# diagram.net
KiCad netlist of a schematic drawn in EasyEDA
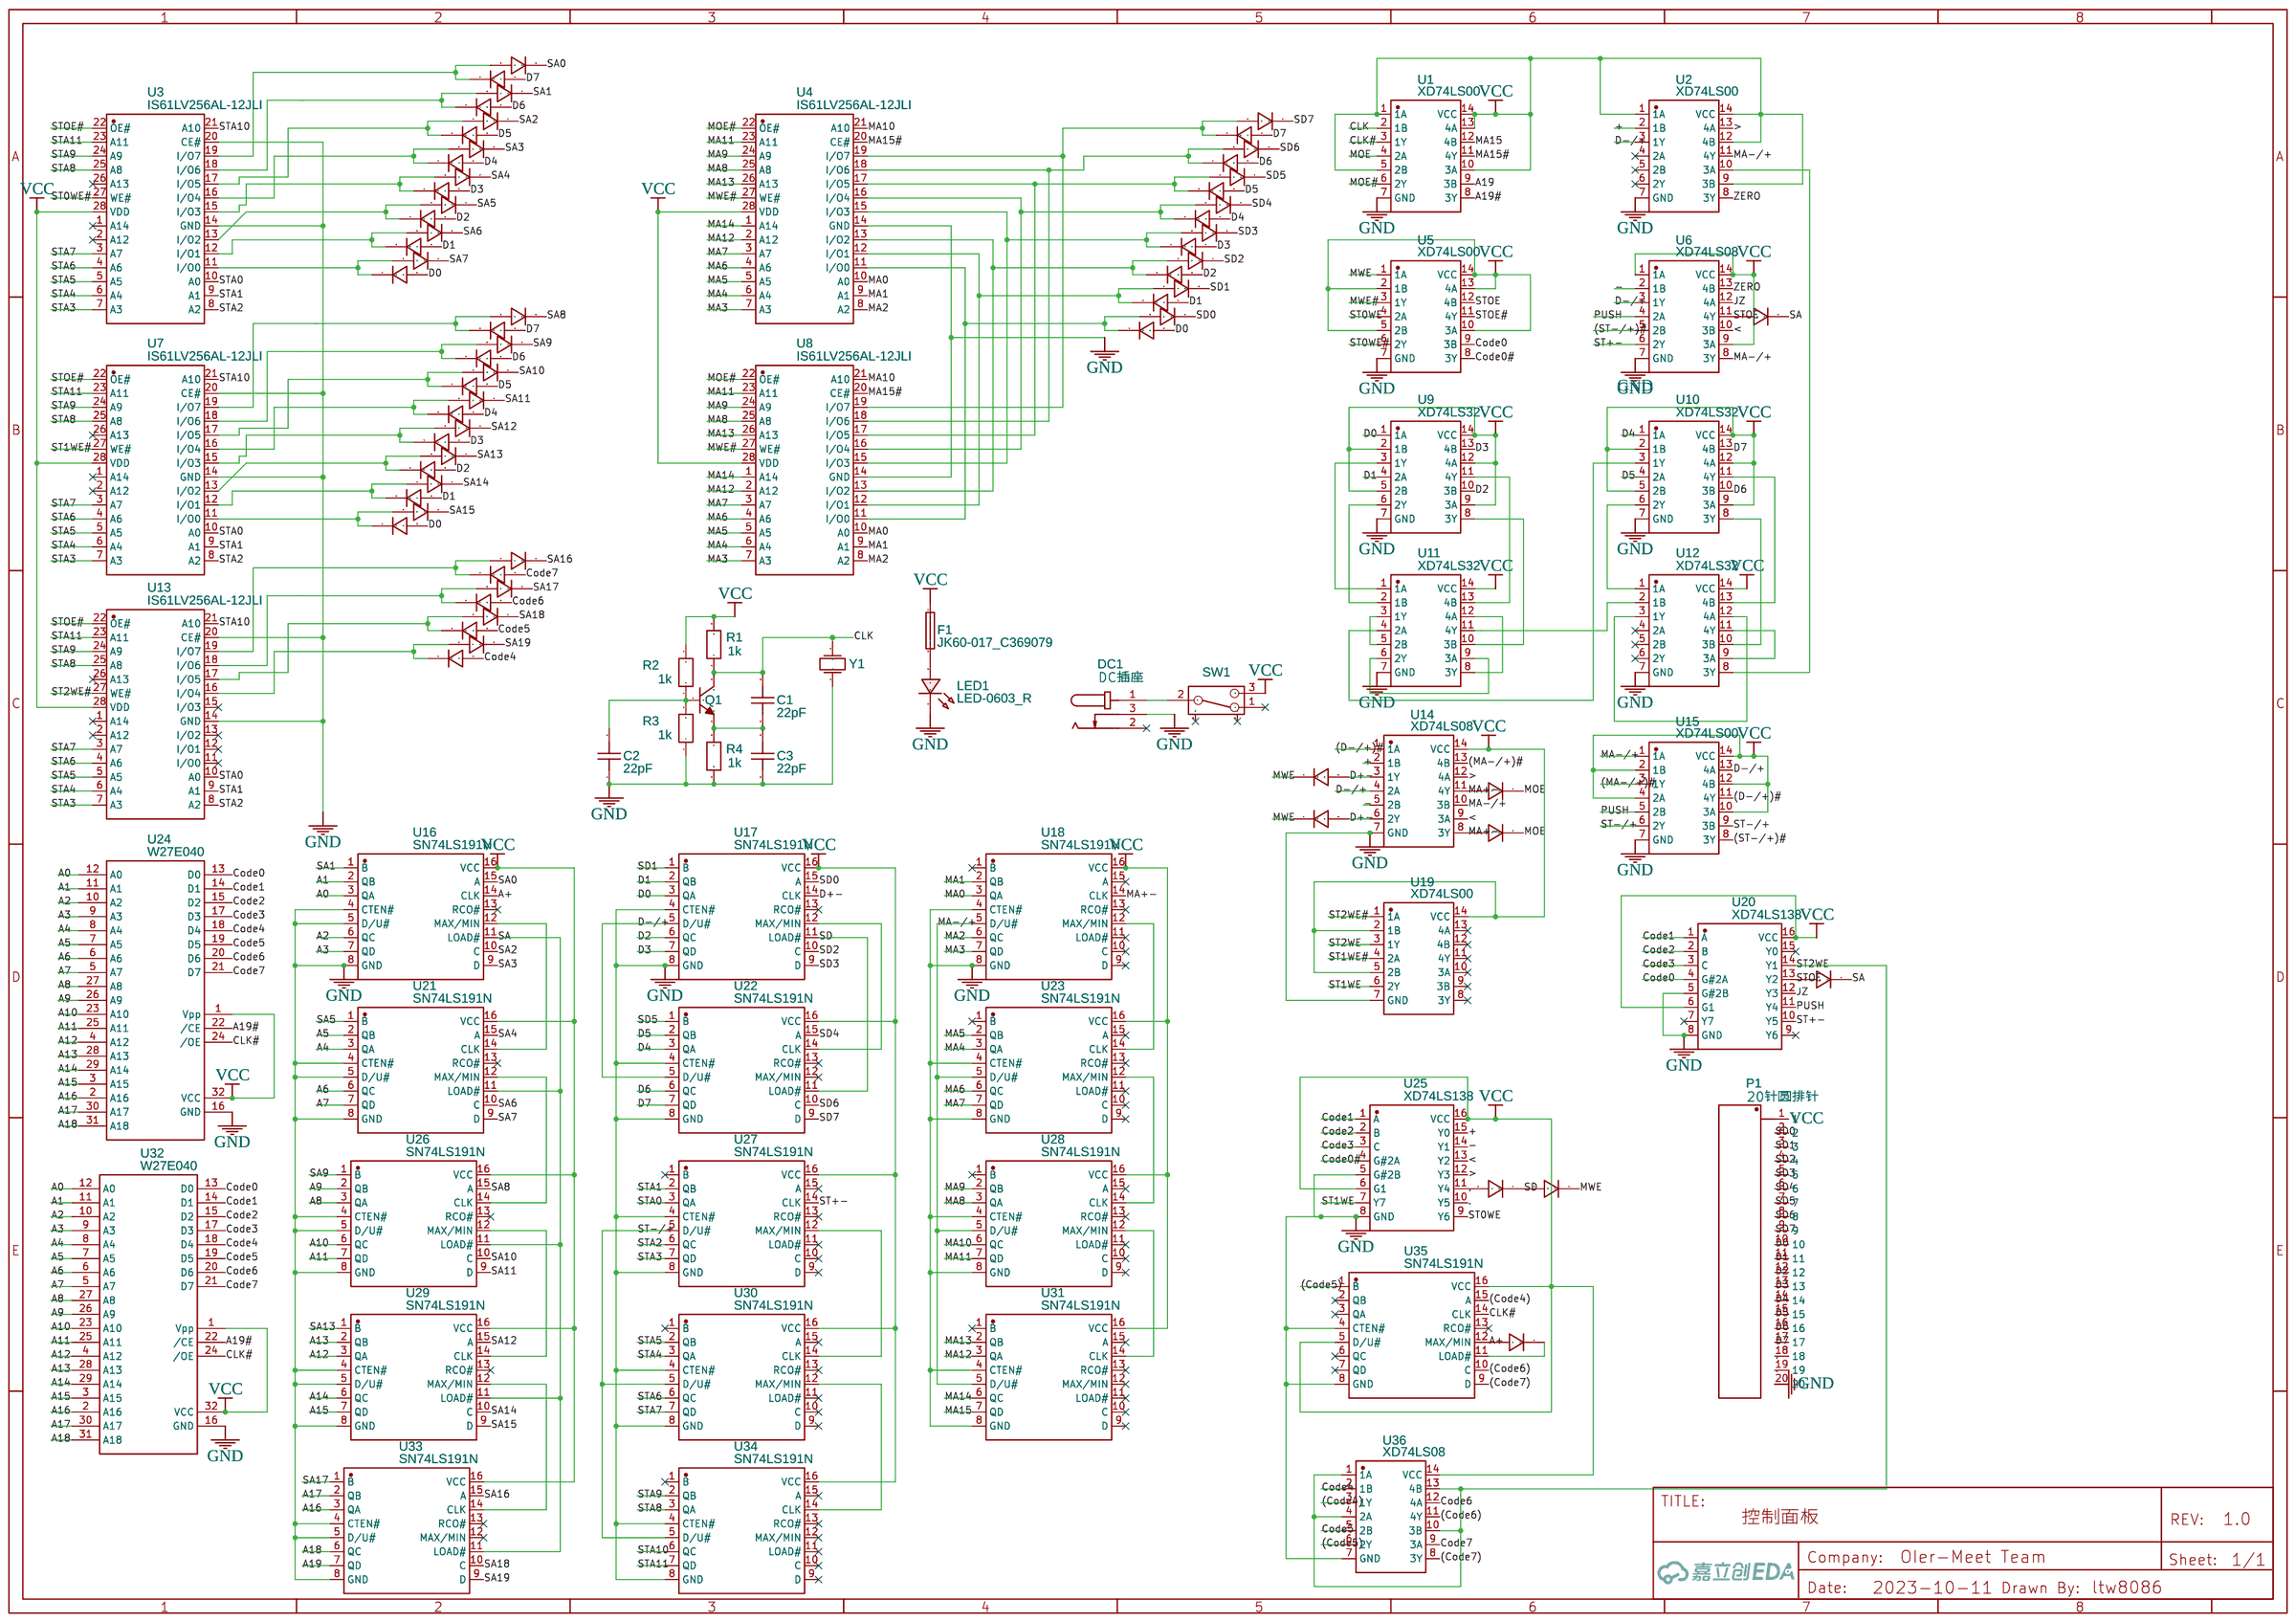
[diagram p0: schematic sheet]

(export (version "E")
  (design (tool "Eeschema 10.0.6"))
  (components
    (comp (ref "C1") (value "22pF") (libsource (lib "") (part "C_RAD-0.2_US")))
    (comp (ref "C2") (value "22pF") (libsource (lib "") (part "C_RAD-0.2_US")))
    (comp (ref "C3") (value "22pF") (libsource (lib "") (part "C_RAD-0.2_US")))
    (comp (ref "D1")
      (value "1N4148")
      (fields (field (name "Manufacturer") "STMicroelectronics"))
      (libsource (lib "") (part "1N4007"))
    )
    (comp (ref "D2")
      (value "1N4148")
      (fields (field (name "Manufacturer") "STMicroelectronics"))
      (libsource (lib "") (part "1N4148"))
    )
    (comp (ref "D3")
      (value "1N4148")
      (fields (field (name "Manufacturer") "STMicroelectronics"))
      (libsource (lib "") (part "1N4007"))
    )
    (comp (ref "D4")
      (value "1N4148")
      (fields (field (name "Manufacturer") "STMicroelectronics"))
      (libsource (lib "") (part "1N4148"))
    )
    (comp (ref "D5")
      (value "1N4148")
      (fields (field (name "Manufacturer") "STMicroelectronics"))
      (libsource (lib "") (part "1N4007"))
    )
    (comp (ref "D6")
      (value "1N4148")
      (fields (field (name "Manufacturer") "STMicroelectronics"))
      (libsource (lib "") (part "1N4007"))
    )
    (comp (ref "D7")
      (value "1N4148")
      (fields (field (name "Manufacturer") "STMicroelectronics"))
      (libsource (lib "") (part "1N4148"))
    )
    (comp (ref "D8")
      (value "1N4148")
      (fields (field (name "Manufacturer") "STMicroelectronics"))
      (libsource (lib "") (part "1N4148"))
    )
    (comp (ref "D9")
      (value "1N4148")
      (fields (field (name "Manufacturer") "STMicroelectronics"))
      (libsource (lib "") (part "1N4007"))
    )
    (comp (ref "D10")
      (value "1N4148")
      (fields (field (name "Manufacturer") "STMicroelectronics"))
      (libsource (lib "") (part "1N4007"))
    )
    (comp (ref "D11")
      (value "1N4148")
      (fields (field (name "Manufacturer") "STMicroelectronics"))
      (libsource (lib "") (part "1N4148"))
    )
    (comp (ref "D12")
      (value "1N4148")
      (fields (field (name "Manufacturer") "STMicroelectronics"))
      (libsource (lib "") (part "1N4148"))
    )
    (comp (ref "D13")
      (value "1N4148")
      (fields (field (name "Manufacturer") "STMicroelectronics"))
      (libsource (lib "") (part "1N4007"))
    )
    (comp (ref "D14")
      (value "1N4148")
      (fields (field (name "Manufacturer") "STMicroelectronics"))
      (libsource (lib "") (part "1N4007"))
    )
    (comp (ref "D15")
      (value "1N4148")
      (fields (field (name "Manufacturer") "STMicroelectronics"))
      (libsource (lib "") (part "1N4148"))
    )
    (comp (ref "D16")
      (value "1N4148")
      (fields (field (name "Manufacturer") "STMicroelectronics"))
      (libsource (lib "") (part "1N4148"))
    )
    (comp (ref "D17")
      (value "1N4148")
      (fields (field (name "Manufacturer") "STMicroelectronics"))
      (libsource (lib "") (part "1N4007"))
    )
    (comp (ref "D18")
      (value "1N4148")
      (fields (field (name "Manufacturer") "STMicroelectronics"))
      (libsource (lib "") (part "1N4007"))
    )
    (comp (ref "D19")
      (value "1N4148")
      (fields (field (name "Manufacturer") "STMicroelectronics"))
      (libsource (lib "") (part "1N4148"))
    )
    (comp (ref "D20")
      (value "1N4148")
      (fields (field (name "Manufacturer") "STMicroelectronics"))
      (libsource (lib "") (part "1N4148"))
    )
    (comp (ref "D21")
      (value "1N4148")
      (fields (field (name "Manufacturer") "STMicroelectronics"))
      (libsource (lib "") (part "1N4007"))
    )
    (comp (ref "D22")
      (value "1N4148")
      (fields (field (name "Manufacturer") "STMicroelectronics"))
      (libsource (lib "") (part "1N4007"))
    )
    (comp (ref "D23")
      (value "1N4148")
      (fields (field (name "Manufacturer") "STMicroelectronics"))
      (libsource (lib "") (part "1N4148"))
    )
    (comp (ref "D24")
      (value "1N4148")
      (fields (field (name "Manufacturer") "STMicroelectronics"))
      (libsource (lib "") (part "1N4148"))
    )
    (comp (ref "D25")
      (value "1N4148")
      (fields (field (name "Manufacturer") "STMicroelectronics"))
      (libsource (lib "") (part "1N4007"))
    )
    (comp (ref "D26")
      (value "1N4148")
      (fields (field (name "Manufacturer") "STMicroelectronics"))
      (libsource (lib "") (part "1N4007"))
    )
    (comp (ref "D27")
      (value "1N4148")
      (fields (field (name "Manufacturer") "STMicroelectronics"))
      (libsource (lib "") (part "1N4148"))
    )
    (comp (ref "D28")
      (value "1N4148")
      (fields (field (name "Manufacturer") "STMicroelectronics"))
      (libsource (lib "") (part "1N4148"))
    )
    (comp (ref "D29")
      (value "1N4148")
      (fields (field (name "Manufacturer") "STMicroelectronics"))
      (libsource (lib "") (part "1N4007"))
    )
    (comp (ref "D30")
      (value "1N4148")
      (fields (field (name "Manufacturer") "STMicroelectronics"))
      (libsource (lib "") (part "1N4148"))
    )
    (comp (ref "D31")
      (value "1N4148")
      (fields (field (name "Manufacturer") "STMicroelectronics"))
      (libsource (lib "") (part "1N4007"))
    )
    (comp (ref "D32")
      (value "1N4148")
      (fields (field (name "Manufacturer") "STMicroelectronics"))
      (libsource (lib "") (part "1N4007"))
    )
    (comp (ref "D33")
      (value "1N4148")
      (fields (field (name "Manufacturer") "STMicroelectronics"))
      (libsource (lib "") (part "1N4148"))
    )
    (comp (ref "D34")
      (value "1N4148")
      (fields (field (name "Manufacturer") "STMicroelectronics"))
      (libsource (lib "") (part "1N4148"))
    )
    (comp (ref "D35")
      (value "1N4148")
      (fields (field (name "Manufacturer") "STMicroelectronics"))
      (libsource (lib "") (part "1N4007"))
    )
    (comp (ref "D36")
      (value "1N4148")
      (fields (field (name "Manufacturer") "STMicroelectronics"))
      (libsource (lib "") (part "1N4148"))
    )
    (comp (ref "D37")
      (value "1N4148")
      (fields (field (name "Manufacturer") "STMicroelectronics"))
      (libsource (lib "") (part "1N4007"))
    )
    (comp (ref "D38")
      (value "1N4148")
      (fields (field (name "Manufacturer") "STMicroelectronics"))
      (libsource (lib "") (part "1N4148"))
    )
    (comp (ref "D39")
      (value "1N4148")
      (fields (field (name "Manufacturer") "STMicroelectronics"))
      (libsource (lib "") (part "1N4007"))
    )
    (comp (ref "D40")
      (value "1N4148")
      (fields (field (name "Manufacturer") "STMicroelectronics"))
      (libsource (lib "") (part "1N4148"))
    )
    (comp (ref "D41")
      (value "1N4148")
      (fields (field (name "Manufacturer") "STMicroelectronics"))
      (libsource (lib "") (part "1N4007"))
    )
    (comp (ref "D42")
      (value "1N4148")
      (fields (field (name "Manufacturer") "STMicroelectronics"))
      (libsource (lib "") (part "1N4148"))
    )
    (comp (ref "D43")
      (value "1N4148")
      (fields (field (name "Manufacturer") "STMicroelectronics"))
      (libsource (lib "") (part "1N4007"))
    )
    (comp (ref "D44")
      (value "1N4148")
      (fields (field (name "Manufacturer") "STMicroelectronics"))
      (libsource (lib "") (part "1N4148"))
    )
    (comp (ref "D45")
      (value "1N4148")
      (fields (field (name "Manufacturer") "STMicroelectronics"))
      (libsource (lib "") (part "1N4007"))
    )
    (comp (ref "D46")
      (value "1N4148")
      (fields (field (name "Manufacturer") "STMicroelectronics"))
      (libsource (lib "") (part "1N4148"))
    )
    (comp (ref "D47")
      (value "1N4148")
      (fields (field (name "Manufacturer") "STMicroelectronics"))
      (libsource (lib "") (part "1N4007"))
    )
    (comp (ref "D48")
      (value "1N4148")
      (fields (field (name "Manufacturer") "STMicroelectronics"))
      (libsource (lib "") (part "1N4148"))
    )
    (comp (ref "D49")
      (value "1N4148")
      (fields (field (name "Manufacturer") "STMicroelectronics"))
      (libsource (lib "") (part "1N4007"))
    )
    (comp (ref "D50")
      (value "1N4148")
      (fields (field (name "Manufacturer") "STMicroelectronics"))
      (libsource (lib "") (part "1N4148"))
    )
    (comp (ref "D51")
      (value "1N4148")
      (fields (field (name "Manufacturer") "STMicroelectronics"))
      (libsource (lib "") (part "1N4007"))
    )
    (comp (ref "D52")
      (value "1N4148")
      (fields (field (name "Manufacturer") "STMicroelectronics"))
      (libsource (lib "") (part "1N4148"))
    )
    (comp (ref "D53")
      (value "1N4148")
      (fields (field (name "Manufacturer") "STMicroelectronics"))
      (libsource (lib "") (part "1N4007"))
    )
    (comp (ref "D54")
      (value "1N4148")
      (fields (field (name "Manufacturer") "STMicroelectronics"))
      (libsource (lib "") (part "1N4148"))
    )
    (comp (ref "D55")
      (value "1N4148")
      (fields (field (name "Manufacturer") "STMicroelectronics"))
      (libsource (lib "") (part "1N4007"))
    )
    (comp (ref "D56")
      (value "1N4148")
      (fields (field (name "Manufacturer") "STMicroelectronics"))
      (libsource (lib "") (part "1N4148"))
    )
    (comp (ref "D57")
      (value "1N4148")
      (fields (field (name "Manufacturer") "STMicroelectronics"))
      (libsource (lib "") (part "1N4148"))
    )
    (comp (ref "D58")
      (value "1N4148")
      (fields (field (name "Manufacturer") "STMicroelectronics"))
      (libsource (lib "") (part "1N4148"))
    )
    (comp (ref "D62")
      (value "1N4148")
      (fields (field (name "Manufacturer") "STMicroelectronics"))
      (libsource (lib "") (part "1N4007"))
    )
    (comp (ref "D63")
      (value "1N4148")
      (fields (field (name "Manufacturer") "STMicroelectronics"))
      (libsource (lib "") (part "1N4007"))
    )
    (comp (ref "D64")
      (value "1N4148")
      (fields (field (name "Manufacturer") "STMicroelectronics"))
      (libsource (lib "") (part "1N4007"))
    )
    (comp (ref "D65")
      (value "1N4148")
      (fields (field (name "Manufacturer") "STMicroelectronics"))
      (libsource (lib "") (part "1N4007"))
    )
    (comp (ref "D66")
      (value "1N4148")
      (fields (field (name "Manufacturer") "STMicroelectronics"))
      (libsource (lib "") (part "1N4148_1"))
    )
    (comp (ref "D67")
      (value "1N4148")
      (fields (field (name "Manufacturer") "STMicroelectronics"))
      (libsource (lib "") (part "1N4007"))
    )
    (comp (ref "D68")
      (value "1N4148")
      (fields (field (name "Manufacturer") "STMicroelectronics"))
      (libsource (lib "") (part "1N4148_1"))
    )
    (comp (ref "DC1")
      (value "DC插座")
      (fields
        (field (name "Manufacturer Part") "DC-005-5A-2.0")
        (field (name "Manufacturer") "XKB Enterprise")
      )
      (libsource (lib "") (part "DC插座"))
    )
    (comp (ref "F1")
      (value "JK60-017_C369079")
      (fields (field (name "Manufacturer Part") "JK60-017") (field (name "Manufacturer") "JK(金科)"))
      (libsource (lib "") (part "JK60-017_C369079"))
    )
    (comp (ref "LED1")
      (value "LED-0603_R")
      (fields
        (field (name "Manufacturer Part") "19-217/R6C-AL1M2VY/3T")
        (field (name "Manufacturer") "EVERLIGHT(台湾亿光)")
      )
      (libsource (lib "") (part "LED-0603_R"))
    )
    (comp (ref "P1")
      (value "20针圆排针")
      (fields (field (name "Manufacturer") "BOOMELE"))
      (libsource (lib "") (part "20针圆排针"))
    )
    (comp (ref "Q1")
      (value "2N3904(TO-92)")
      (fields (field (name "Manufacturer Part") "2N3904") (field (name "Manufacturer") "SEMTECH"))
      (libsource (lib "") (part "2N3904(TO-92)"))
    )
    (comp (ref "R1") (value "1k") (libsource (lib "") (part "R_AXIAL-0.8_EU")))
    (comp (ref "R2") (value "1k") (libsource (lib "") (part "R_AXIAL-0.8_EU")))
    (comp (ref "R3") (value "1k") (libsource (lib "") (part "R_AXIAL-0.8_EU")))
    (comp (ref "R4") (value "1k") (libsource (lib "") (part "R_AXIAL-0.8_EU")))
    (comp (ref "SW1")
      (value "SK-12D02-VG5")
      (fields (field (name "Manufacturer") "Rectangular Connectors - Contacts"))
      (libsource (lib "") (part "SK-12D02-VG5"))
    )
    (comp (ref "U1")
      (value "XD74LS00")
      (fields (field (name "Manufacturer") "XINLUDA(信路达)"))
      (libsource (lib "") (part "XD74LS00"))
    )
    (comp (ref "U2")
      (value "XD74LS00")
      (fields (field (name "Manufacturer") "XINLUDA(信路达)"))
      (libsource (lib "") (part "XD74LS00"))
    )
    (comp (ref "U3")
      (value "IS61LV256AL-12JLI")
      (fields (field (name "Manufacturer") "ISSI(美国芯成)"))
      (libsource (lib "") (part "IS61LV256AL-10TLI"))
    )
    (comp (ref "U4")
      (value "IS61LV256AL-12JLI")
      (fields (field (name "Manufacturer") "ISSI(美国芯成)"))
      (libsource (lib "") (part "IS61LV256AL-10TLI"))
    )
    (comp (ref "U5")
      (value "XD74LS00")
      (fields (field (name "Manufacturer") "XINLUDA(信路达)"))
      (libsource (lib "") (part "XD74LS00"))
    )
    (comp (ref "U6")
      (value "XD74LS08")
      (fields (field (name "Manufacturer") "XINLUDA(信路达)"))
      (libsource (lib "") (part "XD74LS08"))
    )
    (comp (ref "U7")
      (value "IS61LV256AL-12JLI")
      (fields (field (name "Manufacturer") "ISSI(美国芯成)"))
      (libsource (lib "") (part "IS61LV256AL-10TLI"))
    )
    (comp (ref "U8")
      (value "IS61LV256AL-12JLI")
      (fields (field (name "Manufacturer") "ISSI(美国芯成)"))
      (libsource (lib "") (part "IS61LV256AL-10TLI"))
    )
    (comp (ref "U9")
      (value "XD74LS32")
      (fields (field (name "Manufacturer") "XINLUDA(信路达)"))
      (libsource (lib "") (part "XD74LS32"))
    )
    (comp (ref "U10")
      (value "XD74LS32")
      (fields (field (name "Manufacturer") "XINLUDA(信路达)"))
      (libsource (lib "") (part "XD74LS32"))
    )
    (comp (ref "U11")
      (value "XD74LS32")
      (fields (field (name "Manufacturer") "XINLUDA(信路达)"))
      (libsource (lib "") (part "XD74LS32"))
    )
    (comp (ref "U12")
      (value "XD74LS32")
      (fields (field (name "Manufacturer") "XINLUDA(信路达)"))
      (libsource (lib "") (part "XD74LS32"))
    )
    (comp (ref "U13")
      (value "IS61LV256AL-12JLI")
      (fields (field (name "Manufacturer") "ISSI(美国芯成)"))
      (libsource (lib "") (part "IS61LV256AL-10TLI"))
    )
    (comp (ref "U14")
      (value "XD74LS08")
      (fields (field (name "Manufacturer") "XINLUDA(信路达)"))
      (libsource (lib "") (part "XD74LS08"))
    )
    (comp (ref "U15")
      (value "XD74LS00")
      (fields (field (name "Manufacturer") "XINLUDA(信路达)"))
      (libsource (lib "") (part "XD74LS00"))
    )
    (comp (ref "U16")
      (value "SN74LS191N")
      (fields (field (name "Manufacturer") "TI(德州仪器)"))
      (libsource (lib "") (part "SN74LS191N"))
    )
    (comp (ref "U17")
      (value "SN74LS191N")
      (fields (field (name "Manufacturer") "TI(德州仪器)"))
      (libsource (lib "") (part "SN74LS191N"))
    )
    (comp (ref "U18")
      (value "SN74LS191N")
      (fields (field (name "Manufacturer") "TI(德州仪器)"))
      (libsource (lib "") (part "SN74LS191N"))
    )
    (comp (ref "U19")
      (value "XD74LS00")
      (fields (field (name "Manufacturer") "XINLUDA(信路达)"))
      (libsource (lib "") (part "XD74LS00"))
    )
    (comp (ref "U20")
      (value "XD74LS138")
      (fields (field (name "Manufacturer") "XINLUDA"))
      (libsource (lib "") (part "XD74LS138"))
    )
    (comp (ref "U21")
      (value "SN74LS191N")
      (fields (field (name "Manufacturer") "TI(德州仪器)"))
      (libsource (lib "") (part "SN74LS191N"))
    )
    (comp (ref "U22")
      (value "SN74LS191N")
      (fields (field (name "Manufacturer") "TI(德州仪器)"))
      (libsource (lib "") (part "SN74LS191N"))
    )
    (comp (ref "U23")
      (value "SN74LS191N")
      (fields (field (name "Manufacturer") "TI(德州仪器)"))
      (libsource (lib "") (part "SN74LS191N"))
    )
    (comp (ref "U24") (value "W27E040") (libsource (lib "") (part "W27E040")))
    (comp (ref "U25")
      (value "XD74LS138")
      (fields (field (name "Manufacturer") "XINLUDA"))
      (libsource (lib "") (part "XD74LS138"))
    )
    (comp (ref "U26")
      (value "SN74LS191N")
      (fields (field (name "Manufacturer") "TI(德州仪器)"))
      (libsource (lib "") (part "SN74LS191N"))
    )
    (comp (ref "U27")
      (value "SN74LS191N")
      (fields (field (name "Manufacturer") "TI(德州仪器)"))
      (libsource (lib "") (part "SN74LS191N"))
    )
    (comp (ref "U28")
      (value "SN74LS191N")
      (fields (field (name "Manufacturer") "TI(德州仪器)"))
      (libsource (lib "") (part "SN74LS191N"))
    )
    (comp (ref "U29")
      (value "SN74LS191N")
      (fields (field (name "Manufacturer") "TI(德州仪器)"))
      (libsource (lib "") (part "SN74LS191N"))
    )
    (comp (ref "U30")
      (value "SN74LS191N")
      (fields (field (name "Manufacturer") "TI(德州仪器)"))
      (libsource (lib "") (part "SN74LS191N"))
    )
    (comp (ref "U31")
      (value "SN74LS191N")
      (fields (field (name "Manufacturer") "TI(德州仪器)"))
      (libsource (lib "") (part "SN74LS191N"))
    )
    (comp (ref "U32") (value "W27E040") (libsource (lib "") (part "W27E040")))
    (comp (ref "U33")
      (value "SN74LS191N")
      (fields (field (name "Manufacturer") "TI(德州仪器)"))
      (libsource (lib "") (part "SN74LS191N"))
    )
    (comp (ref "U34")
      (value "SN74LS191N")
      (fields (field (name "Manufacturer") "TI(德州仪器)"))
      (libsource (lib "") (part "SN74LS191N"))
    )
    (comp (ref "U35")
      (value "SN74LS191N")
      (fields (field (name "Manufacturer") "TI(德州仪器)"))
      (libsource (lib "") (part "SN74LS191N"))
    )
    (comp (ref "U36")
      (value "XD74LS08")
      (fields (field (name "Manufacturer") "XINLUDA(信路达)"))
      (libsource (lib "") (part "XD74LS08"))
    )
    (comp (ref "Y1") (value "16Mhz 晶振") (libsource (lib "") (part "晶振")))
  )
  (nets
    (net (code "1") (name "/(Code4)") (class "Default")
      (node (ref "U35") (pin "15") (pinfunction "A_15") (pintype "unspecified"))
      (node (ref "U36") (pin "3") (pinfunction "1Y_3") (pintype "unspecified"))
    )
    (net (code "2") (name "/(Code5)") (class "Default")
      (node (ref "U35") (pin "1") (pinfunction "B_1") (pintype "unspecified"))
      (node (ref "U36") (pin "6") (pinfunction "2Y_6") (pintype "unspecified"))
    )
    (net (code "3") (name "/(Code6)") (class "Default")
      (node (ref "U35") (pin "10") (pinfunction "C_10") (pintype "unspecified"))
      (node (ref "U36") (pin "11") (pinfunction "4Y_11") (pintype "unspecified"))
    )
    (net (code "4") (name "/(Code7)") (class "Default")
      (node (ref "U35") (pin "9") (pinfunction "D_9") (pintype "unspecified"))
      (node (ref "U36") (pin "8") (pinfunction "3Y_8") (pintype "unspecified"))
    )
    (net (code "5") (name "/(D-{slash}+)#") (class "Default")
      (node (ref "U14") (pin "1") (pinfunction "1A_1") (pintype "unspecified"))
      (node (ref "U15") (pin "11") (pinfunction "4Y_11") (pintype "unspecified"))
    )
    (net (code "6") (name "/(MA-{slash}+)#") (class "Default")
      (node (ref "U14") (pin "13") (pinfunction "4B_13") (pintype "unspecified"))
      (node (ref "U15") (pin "3") (pinfunction "1Y_3") (pintype "unspecified"))
    )
    (net (code "7") (name "/(ST-{slash}+)#") (class "Default")
      (node (ref "U15") (pin "8") (pinfunction "3Y_8") (pintype "unspecified"))
      (node (ref "U6") (pin "5") (pinfunction "2B_5") (pintype "unspecified"))
    )
    (net (code "8") (name "/+") (class "Default")
      (node (ref "U14") (pin "2") (pinfunction "1B_2") (pintype "unspecified"))
      (node (ref "U2") (pin "2") (pinfunction "1B_2") (pintype "unspecified"))
      (node (ref "U25") (pin "15") (pinfunction "Y0_15") (pintype "unspecified"))
    )
    (net (code "9") (name "/,") (class "Default")
      (node (ref "D62") (pin "2") (pinfunction "2_2") (pintype "unspecified"))
      (node (ref "P1") (pin "18") (pinfunction "18_18") (pintype "unspecified"))
      (node (ref "U25") (pin "11") (pinfunction "Y4_11") (pintype "unspecified"))
    )
    (net (code "10") (name "/-") (class "Default")
      (node (ref "U14") (pin "5") (pinfunction "2B_5") (pintype "unspecified"))
      (node (ref "U25") (pin "14") (pinfunction "Y1_14") (pintype "unspecified"))
      (node (ref "U6") (pin "2") (pinfunction "1B_2") (pintype "unspecified"))
    )
    (net (code "11") (name "/.") (class "Default")
      (node (ref "P1") (pin "19") (pinfunction "19_19") (pintype "unspecified"))
      (node (ref "U25") (pin "10") (pinfunction "Y5_10") (pintype "unspecified"))
    )
    (net (code "12") (name "/<") (class "Default")
      (node (ref "U14") (pin "9") (pinfunction "3A_9") (pintype "unspecified"))
      (node (ref "U25") (pin "13") (pinfunction "Y2_13") (pintype "unspecified"))
      (node (ref "U6") (pin "10") (pinfunction "3B_10") (pintype "unspecified"))
    )
    (net (code "13") (name "/>") (class "Default")
      (node (ref "U14") (pin "12") (pinfunction "4A_12") (pintype "unspecified"))
      (node (ref "U2") (pin "13") (pinfunction "4A_13") (pintype "unspecified"))
      (node (ref "U25") (pin "12") (pinfunction "Y3_12") (pintype "unspecified"))
    )
    (net (code "14") (name "/A+") (class "Default")
      (node (ref "D65") (pin "2") (pinfunction "2_2") (pintype "unspecified"))
      (node (ref "U16") (pin "14") (pinfunction "CLK_14") (pintype "unspecified"))
      (node (ref "U35") (pin "12") (pinfunction "MAX/MIN_12") (pintype "unspecified"))
    )
    (net (code "15") (name "/A0") (class "Default")
      (node (ref "U16") (pin "3") (pinfunction "QA_3") (pintype "unspecified"))
      (node (ref "U24") (pin "12") (pinfunction "A0_12") (pintype "unspecified"))
      (node (ref "U32") (pin "12") (pinfunction "A0_12") (pintype "unspecified"))
    )
    (net (code "16") (name "/A1") (class "Default")
      (node (ref "U16") (pin "2") (pinfunction "QB_2") (pintype "unspecified"))
      (node (ref "U24") (pin "11") (pinfunction "A1_11") (pintype "unspecified"))
      (node (ref "U32") (pin "11") (pinfunction "A1_11") (pintype "unspecified"))
    )
    (net (code "17") (name "/A2") (class "Default")
      (node (ref "U16") (pin "6") (pinfunction "QC_6") (pintype "unspecified"))
      (node (ref "U24") (pin "10") (pinfunction "A2_10") (pintype "unspecified"))
      (node (ref "U32") (pin "10") (pinfunction "A2_10") (pintype "unspecified"))
    )
    (net (code "18") (name "/A3") (class "Default")
      (node (ref "U16") (pin "7") (pinfunction "QD_7") (pintype "unspecified"))
      (node (ref "U24") (pin "9") (pinfunction "A3_9") (pintype "unspecified"))
      (node (ref "U32") (pin "9") (pinfunction "A3_9") (pintype "unspecified"))
    )
    (net (code "19") (name "/A4") (class "Default")
      (node (ref "U21") (pin "3") (pinfunction "QA_3") (pintype "unspecified"))
      (node (ref "U24") (pin "8") (pinfunction "A4_8") (pintype "unspecified"))
      (node (ref "U32") (pin "8") (pinfunction "A4_8") (pintype "unspecified"))
    )
    (net (code "20") (name "/A5") (class "Default")
      (node (ref "U21") (pin "2") (pinfunction "QB_2") (pintype "unspecified"))
      (node (ref "U24") (pin "7") (pinfunction "A5_7") (pintype "unspecified"))
      (node (ref "U32") (pin "7") (pinfunction "A5_7") (pintype "unspecified"))
    )
    (net (code "21") (name "/A6") (class "Default")
      (node (ref "U21") (pin "6") (pinfunction "QC_6") (pintype "unspecified"))
      (node (ref "U24") (pin "6") (pinfunction "A6_6") (pintype "unspecified"))
      (node (ref "U32") (pin "6") (pinfunction "A6_6") (pintype "unspecified"))
    )
    (net (code "22") (name "/A7") (class "Default")
      (node (ref "U21") (pin "7") (pinfunction "QD_7") (pintype "unspecified"))
      (node (ref "U24") (pin "5") (pinfunction "A7_5") (pintype "unspecified"))
      (node (ref "U32") (pin "5") (pinfunction "A7_5") (pintype "unspecified"))
    )
    (net (code "23") (name "/A8") (class "Default")
      (node (ref "U24") (pin "27") (pinfunction "A8_27") (pintype "unspecified"))
      (node (ref "U26") (pin "3") (pinfunction "QA_3") (pintype "unspecified"))
      (node (ref "U32") (pin "27") (pinfunction "A8_27") (pintype "unspecified"))
    )
    (net (code "24") (name "/A9") (class "Default")
      (node (ref "U24") (pin "26") (pinfunction "A9_26") (pintype "unspecified"))
      (node (ref "U26") (pin "2") (pinfunction "QB_2") (pintype "unspecified"))
      (node (ref "U32") (pin "26") (pinfunction "A9_26") (pintype "unspecified"))
    )
    (net (code "25") (name "/A10") (class "Default")
      (node (ref "U24") (pin "23") (pinfunction "A10_23") (pintype "unspecified"))
      (node (ref "U26") (pin "6") (pinfunction "QC_6") (pintype "unspecified"))
      (node (ref "U32") (pin "23") (pinfunction "A10_23") (pintype "unspecified"))
    )
    (net (code "26") (name "/A11") (class "Default")
      (node (ref "U24") (pin "25") (pinfunction "A11_25") (pintype "unspecified"))
      (node (ref "U26") (pin "7") (pinfunction "QD_7") (pintype "unspecified"))
      (node (ref "U32") (pin "25") (pinfunction "A11_25") (pintype "unspecified"))
    )
    (net (code "27") (name "/A12") (class "Default")
      (node (ref "U24") (pin "4") (pinfunction "A12_4") (pintype "unspecified"))
      (node (ref "U29") (pin "3") (pinfunction "QA_3") (pintype "unspecified"))
      (node (ref "U32") (pin "4") (pinfunction "A12_4") (pintype "unspecified"))
    )
    (net (code "28") (name "/A13") (class "Default")
      (node (ref "U24") (pin "28") (pinfunction "A13_28") (pintype "unspecified"))
      (node (ref "U29") (pin "2") (pinfunction "QB_2") (pintype "unspecified"))
      (node (ref "U32") (pin "28") (pinfunction "A13_28") (pintype "unspecified"))
    )
    (net (code "29") (name "/A14") (class "Default")
      (node (ref "U24") (pin "29") (pinfunction "A14_29") (pintype "unspecified"))
      (node (ref "U29") (pin "6") (pinfunction "QC_6") (pintype "unspecified"))
      (node (ref "U32") (pin "29") (pinfunction "A14_29") (pintype "unspecified"))
    )
    (net (code "30") (name "/A15") (class "Default")
      (node (ref "U24") (pin "3") (pinfunction "A15_3") (pintype "unspecified"))
      (node (ref "U29") (pin "7") (pinfunction "QD_7") (pintype "unspecified"))
      (node (ref "U32") (pin "3") (pinfunction "A15_3") (pintype "unspecified"))
    )
    (net (code "31") (name "/A16") (class "Default")
      (node (ref "U24") (pin "2") (pinfunction "A16_2") (pintype "unspecified"))
      (node (ref "U32") (pin "2") (pinfunction "A16_2") (pintype "unspecified"))
      (node (ref "U33") (pin "3") (pinfunction "QA_3") (pintype "unspecified"))
    )
    (net (code "32") (name "/A17") (class "Default")
      (node (ref "U24") (pin "30") (pinfunction "A17_30") (pintype "unspecified"))
      (node (ref "U32") (pin "30") (pinfunction "A17_30") (pintype "unspecified"))
      (node (ref "U33") (pin "2") (pinfunction "QB_2") (pintype "unspecified"))
    )
    (net (code "33") (name "/A18") (class "Default")
      (node (ref "U24") (pin "31") (pinfunction "A18_31") (pintype "unspecified"))
      (node (ref "U32") (pin "31") (pinfunction "A18_31") (pintype "unspecified"))
      (node (ref "U33") (pin "6") (pinfunction "QC_6") (pintype "unspecified"))
    )
    (net (code "34") (name "/A19") (class "Default")
      (node (ref "U1") (pin "9") (pinfunction "3B_9") (pintype "unspecified"))
      (node (ref "U33") (pin "7") (pinfunction "QD_7") (pintype "unspecified"))
    )
    (net (code "35") (name "/A19#") (class "Default")
      (node (ref "U1") (pin "8") (pinfunction "3Y_8") (pintype "unspecified"))
      (node (ref "U24") (pin "22") (pinfunction "/CE_22") (pintype "unspecified"))
      (node (ref "U32") (pin "22") (pinfunction "/CE_22") (pintype "unspecified"))
    )
    (net (code "36") (name "/CLK") (class "Default")
      (node (ref "C1") (pin "2") (pinfunction "2_2") (pintype "unspecified"))
      (node (ref "Q1") (pin "3") (pinfunction "C_3") (pintype "unspecified"))
      (node (ref "R1") (pin "1") (pinfunction "1_1") (pintype "unspecified"))
      (node (ref "U1") (pin "2") (pinfunction "1B_2") (pintype "unspecified"))
      (node (ref "Y1") (pin "2") (pinfunction "P2_2") (pintype "unspecified"))
    )
    (net (code "37") (name "/CLK#") (class "Default")
      (node (ref "U1") (pin "3") (pinfunction "1Y_3") (pintype "unspecified"))
      (node (ref "U24") (pin "24") (pinfunction "/OE_24") (pintype "unspecified"))
      (node (ref "U32") (pin "24") (pinfunction "/OE_24") (pintype "unspecified"))
      (node (ref "U35") (pin "14") (pinfunction "CLK_14") (pintype "unspecified"))
    )
    (net (code "38") (name "/Code0") (class "Default")
      (node (ref "U20") (pin "4") (pinfunction "G#2A_4") (pintype "unspecified"))
      (node (ref "U24") (pin "13") (pinfunction "D0_13") (pintype "unspecified"))
      (node (ref "U32") (pin "13") (pinfunction "D0_13") (pintype "unspecified"))
      (node (ref "U5") (pin "9") (pinfunction "3B_9") (pintype "unspecified"))
    )
    (net (code "39") (name "/Code0#") (class "Default")
      (node (ref "U25") (pin "4") (pinfunction "G#2A_4") (pintype "unspecified"))
      (node (ref "U5") (pin "8") (pinfunction "3Y_8") (pintype "unspecified"))
    )
    (net (code "40") (name "/Code1") (class "Default")
      (node (ref "U20") (pin "1") (pinfunction "A_1") (pintype "unspecified"))
      (node (ref "U24") (pin "14") (pinfunction "D1_14") (pintype "unspecified"))
      (node (ref "U25") (pin "1") (pinfunction "A_1") (pintype "unspecified"))
      (node (ref "U32") (pin "14") (pinfunction "D1_14") (pintype "unspecified"))
    )
    (net (code "41") (name "/Code2") (class "Default")
      (node (ref "U20") (pin "2") (pinfunction "B_2") (pintype "unspecified"))
      (node (ref "U24") (pin "15") (pinfunction "D2_15") (pintype "unspecified"))
      (node (ref "U25") (pin "2") (pinfunction "B_2") (pintype "unspecified"))
      (node (ref "U32") (pin "15") (pinfunction "D2_15") (pintype "unspecified"))
    )
    (net (code "42") (name "/Code3") (class "Default")
      (node (ref "U20") (pin "3") (pinfunction "C_3") (pintype "unspecified"))
      (node (ref "U24") (pin "17") (pinfunction "D3_17") (pintype "unspecified"))
      (node (ref "U25") (pin "3") (pinfunction "C_3") (pintype "unspecified"))
      (node (ref "U32") (pin "17") (pinfunction "D3_17") (pintype "unspecified"))
    )
    (net (code "43") (name "/Code4") (class "Default")
      (node (ref "D56") (pin "2") (pinfunction "2_2") (pintype "unspecified"))
      (node (ref "U24") (pin "18") (pinfunction "D4_18") (pintype "unspecified"))
      (node (ref "U32") (pin "18") (pinfunction "D4_18") (pintype "unspecified"))
      (node (ref "U36") (pin "2") (pinfunction "1B_2") (pintype "unspecified"))
    )
    (net (code "44") (name "/Code5") (class "Default")
      (node (ref "D54") (pin "2") (pinfunction "2_2") (pintype "unspecified"))
      (node (ref "U24") (pin "19") (pinfunction "D5_19") (pintype "unspecified"))
      (node (ref "U32") (pin "19") (pinfunction "D5_19") (pintype "unspecified"))
      (node (ref "U36") (pin "5") (pinfunction "2B_5") (pintype "unspecified"))
    )
    (net (code "45") (name "/Code6") (class "Default")
      (node (ref "D52") (pin "2") (pinfunction "2_2") (pintype "unspecified"))
      (node (ref "U24") (pin "20") (pinfunction "D6_20") (pintype "unspecified"))
      (node (ref "U32") (pin "20") (pinfunction "D6_20") (pintype "unspecified"))
      (node (ref "U36") (pin "12") (pinfunction "4A_12") (pintype "unspecified"))
    )
    (net (code "46") (name "/Code7") (class "Default")
      (node (ref "D50") (pin "2") (pinfunction "2_2") (pintype "unspecified"))
      (node (ref "U24") (pin "21") (pinfunction "D7_21") (pintype "unspecified"))
      (node (ref "U32") (pin "21") (pinfunction "D7_21") (pintype "unspecified"))
      (node (ref "U36") (pin "9") (pinfunction "3A_9") (pintype "unspecified"))
    )
    (net (code "47") (name "/D+-") (class "Default")
      (node (ref "D57") (pin "2") (pinfunction "2_2") (pintype "unspecified"))
      (node (ref "D58") (pin "2") (pinfunction "2_2") (pintype "unspecified"))
      (node (ref "U14") (pin "3") (pinfunction "1Y_3") (pintype "unspecified"))
      (node (ref "U14") (pin "6") (pinfunction "2Y_6") (pintype "unspecified"))
      (node (ref "U17") (pin "14") (pinfunction "CLK_14") (pintype "unspecified"))
    )
    (net (code "48") (name "/D-{slash}+") (class "Default")
      (node (ref "U14") (pin "4") (pinfunction "2A_4") (pintype "unspecified"))
      (node (ref "U15") (pin "13") (pinfunction "4A_13") (pintype "unspecified"))
      (node (ref "U17") (pin "5") (pinfunction "D/U#_5") (pintype "unspecified"))
      (node (ref "U2") (pin "3") (pinfunction "1Y_3") (pintype "unspecified"))
      (node (ref "U22") (pin "5") (pinfunction "D/U#_5") (pintype "unspecified"))
      (node (ref "U6") (pin "3") (pinfunction "1Y_3") (pintype "unspecified"))
    )
    (net (code "49") (name "/D0") (class "Default")
      (node (ref "D27") (pin "2") (pinfunction "2_2") (pintype "unspecified"))
      (node (ref "D34") (pin "2") (pinfunction "2_2") (pintype "unspecified"))
      (node (ref "D48") (pin "2") (pinfunction "2_2") (pintype "unspecified"))
      (node (ref "P1") (pin "10") (pinfunction "10_10") (pintype "unspecified"))
      (node (ref "U17") (pin "3") (pinfunction "QA_3") (pintype "unspecified"))
      (node (ref "U9") (pin "1") (pinfunction "1A_1") (pintype "unspecified"))
    )
    (net (code "50") (name "/D1") (class "Default")
      (node (ref "D23") (pin "2") (pinfunction "2_2") (pintype "unspecified"))
      (node (ref "D30") (pin "2") (pinfunction "2_2") (pintype "unspecified"))
      (node (ref "D46") (pin "2") (pinfunction "2_2") (pintype "unspecified"))
      (node (ref "P1") (pin "11") (pinfunction "11_11") (pintype "unspecified"))
      (node (ref "U17") (pin "2") (pinfunction "QB_2") (pintype "unspecified"))
      (node (ref "U9") (pin "4") (pinfunction "2A_4") (pintype "unspecified"))
    )
    (net (code "51") (name "/D2") (class "Default")
      (node (ref "D19") (pin "2") (pinfunction "2_2") (pintype "unspecified"))
      (node (ref "D28") (pin "2") (pinfunction "2_2") (pintype "unspecified"))
      (node (ref "D44") (pin "2") (pinfunction "2_2") (pintype "unspecified"))
      (node (ref "P1") (pin "12") (pinfunction "12_12") (pintype "unspecified"))
      (node (ref "U17") (pin "6") (pinfunction "QC_6") (pintype "unspecified"))
      (node (ref "U9") (pin "10") (pinfunction "3B_10") (pintype "unspecified"))
    )
    (net (code "52") (name "/D3") (class "Default")
      (node (ref "D15") (pin "2") (pinfunction "2_2") (pintype "unspecified"))
      (node (ref "D24") (pin "2") (pinfunction "2_2") (pintype "unspecified"))
      (node (ref "D42") (pin "2") (pinfunction "2_2") (pintype "unspecified"))
      (node (ref "P1") (pin "13") (pinfunction "13_13") (pintype "unspecified"))
      (node (ref "U17") (pin "7") (pinfunction "QD_7") (pintype "unspecified"))
      (node (ref "U9") (pin "13") (pinfunction "4B_13") (pintype "unspecified"))
    )
    (net (code "53") (name "/D4") (class "Default")
      (node (ref "D11") (pin "2") (pinfunction "2_2") (pintype "unspecified"))
      (node (ref "D20") (pin "2") (pinfunction "2_2") (pintype "unspecified"))
      (node (ref "D40") (pin "2") (pinfunction "2_2") (pintype "unspecified"))
      (node (ref "P1") (pin "14") (pinfunction "14_14") (pintype "unspecified"))
      (node (ref "U10") (pin "1") (pinfunction "1A_1") (pintype "unspecified"))
      (node (ref "U22") (pin "3") (pinfunction "QA_3") (pintype "unspecified"))
    )
    (net (code "54") (name "/D5") (class "Default")
      (node (ref "D16") (pin "2") (pinfunction "2_2") (pintype "unspecified"))
      (node (ref "D38") (pin "2") (pinfunction "2_2") (pintype "unspecified"))
      (node (ref "D7") (pin "2") (pinfunction "2_2") (pintype "unspecified"))
      (node (ref "P1") (pin "15") (pinfunction "15_15") (pintype "unspecified"))
      (node (ref "U10") (pin "4") (pinfunction "2A_4") (pintype "unspecified"))
      (node (ref "U22") (pin "2") (pinfunction "QB_2") (pintype "unspecified"))
    )
    (net (code "55") (name "/D6") (class "Default")
      (node (ref "D12") (pin "2") (pinfunction "2_2") (pintype "unspecified"))
      (node (ref "D36") (pin "2") (pinfunction "2_2") (pintype "unspecified"))
      (node (ref "D4") (pin "2") (pinfunction "2_2") (pintype "unspecified"))
      (node (ref "P1") (pin "16") (pinfunction "16_16") (pintype "unspecified"))
      (node (ref "U10") (pin "10") (pinfunction "3B_10") (pintype "unspecified"))
      (node (ref "U22") (pin "6") (pinfunction "QC_6") (pintype "unspecified"))
    )
    (net (code "56") (name "/D7") (class "Default")
      (node (ref "D2") (pin "2") (pinfunction "2_2") (pintype "unspecified"))
      (node (ref "D33") (pin "2") (pinfunction "2_2") (pintype "unspecified"))
      (node (ref "D8") (pin "2") (pinfunction "2_2") (pintype "unspecified"))
      (node (ref "P1") (pin "17") (pinfunction "17_17") (pintype "unspecified"))
      (node (ref "U10") (pin "13") (pinfunction "4B_13") (pintype "unspecified"))
      (node (ref "U22") (pin "7") (pinfunction "QD_7") (pintype "unspecified"))
    )
    (net (code "57") (name "/JZ") (class "Default")
      (node (ref "U20") (pin "12") (pinfunction "Y3_12") (pintype "unspecified"))
      (node (ref "U6") (pin "12") (pinfunction "4A_12") (pintype "unspecified"))
    )
    (net (code "58") (name "/MA+-") (class "Default")
      (node (ref "D63") (pin "2") (pinfunction "2_2") (pintype "unspecified"))
      (node (ref "D64") (pin "2") (pinfunction "2_2") (pintype "unspecified"))
      (node (ref "U14") (pin "11") (pinfunction "4Y_11") (pintype "unspecified"))
      (node (ref "U14") (pin "8") (pinfunction "3Y_8") (pintype "unspecified"))
      (node (ref "U18") (pin "14") (pinfunction "CLK_14") (pintype "unspecified"))
    )
    (net (code "59") (name "/MA-{slash}+") (class "Default")
      (node (ref "U14") (pin "10") (pinfunction "3B_10") (pintype "unspecified"))
      (node (ref "U15") (pin "1") (pinfunction "1A_1") (pintype "unspecified"))
      (node (ref "U18") (pin "5") (pinfunction "D/U#_5") (pintype "unspecified"))
      (node (ref "U2") (pin "11") (pinfunction "4Y_11") (pintype "unspecified"))
      (node (ref "U23") (pin "5") (pinfunction "D/U#_5") (pintype "unspecified"))
      (node (ref "U28") (pin "5") (pinfunction "D/U#_5") (pintype "unspecified"))
      (node (ref "U31") (pin "5") (pinfunction "D/U#_5") (pintype "unspecified"))
      (node (ref "U6") (pin "8") (pinfunction "3Y_8") (pintype "unspecified"))
    )
    (net (code "60") (name "/MA0") (class "Default")
      (node (ref "U18") (pin "3") (pinfunction "QA_3") (pintype "unspecified"))
      (node (ref "U4") (pin "10") (pinfunction "A0_10") (pintype "unspecified"))
      (node (ref "U8") (pin "10") (pinfunction "A0_10") (pintype "unspecified"))
    )
    (net (code "61") (name "/MA1") (class "Default")
      (node (ref "U18") (pin "2") (pinfunction "QB_2") (pintype "unspecified"))
      (node (ref "U4") (pin "9") (pinfunction "A1_9") (pintype "unspecified"))
      (node (ref "U8") (pin "9") (pinfunction "A1_9") (pintype "unspecified"))
    )
    (net (code "62") (name "/MA2") (class "Default")
      (node (ref "U18") (pin "6") (pinfunction "QC_6") (pintype "unspecified"))
      (node (ref "U4") (pin "8") (pinfunction "A2_8") (pintype "unspecified"))
      (node (ref "U8") (pin "8") (pinfunction "A2_8") (pintype "unspecified"))
    )
    (net (code "63") (name "/MA3") (class "Default")
      (node (ref "U18") (pin "7") (pinfunction "QD_7") (pintype "unspecified"))
      (node (ref "U4") (pin "7") (pinfunction "A3_7") (pintype "unspecified"))
      (node (ref "U8") (pin "7") (pinfunction "A3_7") (pintype "unspecified"))
    )
    (net (code "64") (name "/MA4") (class "Default")
      (node (ref "U23") (pin "3") (pinfunction "QA_3") (pintype "unspecified"))
      (node (ref "U4") (pin "6") (pinfunction "A4_6") (pintype "unspecified"))
      (node (ref "U8") (pin "6") (pinfunction "A4_6") (pintype "unspecified"))
    )
    (net (code "65") (name "/MA5") (class "Default")
      (node (ref "U23") (pin "2") (pinfunction "QB_2") (pintype "unspecified"))
      (node (ref "U4") (pin "5") (pinfunction "A5_5") (pintype "unspecified"))
      (node (ref "U8") (pin "5") (pinfunction "A5_5") (pintype "unspecified"))
    )
    (net (code "66") (name "/MA6") (class "Default")
      (node (ref "U23") (pin "6") (pinfunction "QC_6") (pintype "unspecified"))
      (node (ref "U4") (pin "4") (pinfunction "A6_4") (pintype "unspecified"))
      (node (ref "U8") (pin "4") (pinfunction "A6_4") (pintype "unspecified"))
    )
    (net (code "67") (name "/MA7") (class "Default")
      (node (ref "U23") (pin "7") (pinfunction "QD_7") (pintype "unspecified"))
      (node (ref "U4") (pin "3") (pinfunction "A7_3") (pintype "unspecified"))
      (node (ref "U8") (pin "3") (pinfunction "A7_3") (pintype "unspecified"))
    )
    (net (code "68") (name "/MA8") (class "Default")
      (node (ref "U28") (pin "3") (pinfunction "QA_3") (pintype "unspecified"))
      (node (ref "U4") (pin "25") (pinfunction "A8_25") (pintype "unspecified"))
      (node (ref "U8") (pin "25") (pinfunction "A8_25") (pintype "unspecified"))
    )
    (net (code "69") (name "/MA9") (class "Default")
      (node (ref "U28") (pin "2") (pinfunction "QB_2") (pintype "unspecified"))
      (node (ref "U4") (pin "24") (pinfunction "A9_24") (pintype "unspecified"))
      (node (ref "U8") (pin "24") (pinfunction "A9_24") (pintype "unspecified"))
    )
    (net (code "70") (name "/MA10") (class "Default")
      (node (ref "U28") (pin "6") (pinfunction "QC_6") (pintype "unspecified"))
      (node (ref "U4") (pin "21") (pinfunction "A10_21") (pintype "unspecified"))
      (node (ref "U8") (pin "21") (pinfunction "A10_21") (pintype "unspecified"))
    )
    (net (code "71") (name "/MA11") (class "Default")
      (node (ref "U28") (pin "7") (pinfunction "QD_7") (pintype "unspecified"))
      (node (ref "U4") (pin "23") (pinfunction "A11_23") (pintype "unspecified"))
      (node (ref "U8") (pin "23") (pinfunction "A11_23") (pintype "unspecified"))
    )
    (net (code "72") (name "/MA12") (class "Default")
      (node (ref "U31") (pin "3") (pinfunction "QA_3") (pintype "unspecified"))
      (node (ref "U4") (pin "2") (pinfunction "A12_2") (pintype "unspecified"))
      (node (ref "U8") (pin "2") (pinfunction "A12_2") (pintype "unspecified"))
    )
    (net (code "73") (name "/MA13") (class "Default")
      (node (ref "U31") (pin "2") (pinfunction "QB_2") (pintype "unspecified"))
      (node (ref "U4") (pin "26") (pinfunction "A13_26") (pintype "unspecified"))
      (node (ref "U8") (pin "26") (pinfunction "A13_26") (pintype "unspecified"))
    )
    (net (code "74") (name "/MA14") (class "Default")
      (node (ref "U31") (pin "6") (pinfunction "QC_6") (pintype "unspecified"))
      (node (ref "U4") (pin "1") (pinfunction "A14_1") (pintype "unspecified"))
      (node (ref "U8") (pin "1") (pinfunction "A14_1") (pintype "unspecified"))
    )
    (net (code "75") (name "/MA15") (class "Default")
      (node (ref "U1") (pin "12") (pinfunction "4B_12") (pintype "unspecified"))
      (node (ref "U31") (pin "7") (pinfunction "QD_7") (pintype "unspecified"))
    )
    (net (code "76") (name "/MA15#") (class "Default")
      (node (ref "U1") (pin "11") (pinfunction "4Y_11") (pintype "unspecified"))
      (node (ref "U4") (pin "20") (pinfunction "CE#_20") (pintype "unspecified"))
      (node (ref "U8") (pin "20") (pinfunction "CE#_20") (pintype "unspecified"))
    )
    (net (code "77") (name "/MOE") (class "Default")
      (node (ref "D63") (pin "1") (pinfunction "1_1") (pintype "unspecified"))
      (node (ref "D64") (pin "1") (pinfunction "1_1") (pintype "unspecified"))
      (node (ref "U1") (pin "4") (pinfunction "2A_4") (pintype "unspecified"))
    )
    (net (code "78") (name "/MOE#") (class "Default")
      (node (ref "U1") (pin "6") (pinfunction "2Y_6") (pintype "unspecified"))
      (node (ref "U4") (pin "22") (pinfunction "OE#_22") (pintype "unspecified"))
      (node (ref "U8") (pin "22") (pinfunction "OE#_22") (pintype "unspecified"))
    )
    (net (code "79") (name "/MWE") (class "Default")
      (node (ref "D57") (pin "1") (pinfunction "1_1") (pintype "unspecified"))
      (node (ref "D58") (pin "1") (pinfunction "1_1") (pintype "unspecified"))
      (node (ref "D67") (pin "1") (pinfunction "1_1") (pintype "unspecified"))
      (node (ref "U5") (pin "1") (pinfunction "1A_1") (pintype "unspecified"))
    )
    (net (code "80") (name "/MWE#") (class "Default")
      (node (ref "U4") (pin "27") (pinfunction "WE#_27") (pintype "unspecified"))
      (node (ref "U5") (pin "3") (pinfunction "1Y_3") (pintype "unspecified"))
      (node (ref "U8") (pin "27") (pinfunction "WE#_27") (pintype "unspecified"))
    )
    (net (code "81") (name "/PUSH") (class "Default")
      (node (ref "U15") (pin "5") (pinfunction "2B_5") (pintype "unspecified"))
      (node (ref "U20") (pin "11") (pinfunction "Y4_11") (pintype "unspecified"))
      (node (ref "U6") (pin "4") (pinfunction "2A_4") (pintype "unspecified"))
    )
    (net (code "82") (name "/SA") (class "Default")
      (node (ref "D66") (pin "1") (pinfunction "1_1") (pintype "unspecified"))
      (node (ref "D68") (pin "1") (pinfunction "1_1") (pintype "unspecified"))
      (node (ref "U16") (pin "11") (pinfunction "LOAD#_11") (pintype "unspecified"))
      (node (ref "U21") (pin "11") (pinfunction "LOAD#_11") (pintype "unspecified"))
      (node (ref "U26") (pin "11") (pinfunction "LOAD#_11") (pintype "unspecified"))
      (node (ref "U29") (pin "11") (pinfunction "LOAD#_11") (pintype "unspecified"))
      (node (ref "U33") (pin "11") (pinfunction "LOAD#_11") (pintype "unspecified"))
    )
    (net (code "83") (name "/SA0") (class "Default")
      (node (ref "D1") (pin "1") (pinfunction "1_1") (pintype "unspecified"))
      (node (ref "U16") (pin "15") (pinfunction "A_15") (pintype "unspecified"))
    )
    (net (code "84") (name "/SA1") (class "Default")
      (node (ref "D3") (pin "1") (pinfunction "1_1") (pintype "unspecified"))
      (node (ref "U16") (pin "1") (pinfunction "B_1") (pintype "unspecified"))
    )
    (net (code "85") (name "/SA2") (class "Default")
      (node (ref "D5") (pin "1") (pinfunction "1_1") (pintype "unspecified"))
      (node (ref "U16") (pin "10") (pinfunction "C_10") (pintype "unspecified"))
    )
    (net (code "86") (name "/SA3") (class "Default")
      (node (ref "D9") (pin "1") (pinfunction "1_1") (pintype "unspecified"))
      (node (ref "U16") (pin "9") (pinfunction "D_9") (pintype "unspecified"))
    )
    (net (code "87") (name "/SA4") (class "Default")
      (node (ref "D13") (pin "1") (pinfunction "1_1") (pintype "unspecified"))
      (node (ref "U21") (pin "15") (pinfunction "A_15") (pintype "unspecified"))
    )
    (net (code "88") (name "/SA5") (class "Default")
      (node (ref "D17") (pin "1") (pinfunction "1_1") (pintype "unspecified"))
      (node (ref "U21") (pin "1") (pinfunction "B_1") (pintype "unspecified"))
    )
    (net (code "89") (name "/SA6") (class "Default")
      (node (ref "D21") (pin "1") (pinfunction "1_1") (pintype "unspecified"))
      (node (ref "U21") (pin "10") (pinfunction "C_10") (pintype "unspecified"))
    )
    (net (code "90") (name "/SA7") (class "Default")
      (node (ref "D25") (pin "1") (pinfunction "1_1") (pintype "unspecified"))
      (node (ref "U21") (pin "9") (pinfunction "D_9") (pintype "unspecified"))
    )
    (net (code "91") (name "/SA8") (class "Default")
      (node (ref "D31") (pin "1") (pinfunction "1_1") (pintype "unspecified"))
      (node (ref "U26") (pin "15") (pinfunction "A_15") (pintype "unspecified"))
    )
    (net (code "92") (name "/SA9") (class "Default")
      (node (ref "D35") (pin "1") (pinfunction "1_1") (pintype "unspecified"))
      (node (ref "U26") (pin "1") (pinfunction "B_1") (pintype "unspecified"))
    )
    (net (code "93") (name "/SA10") (class "Default")
      (node (ref "D37") (pin "1") (pinfunction "1_1") (pintype "unspecified"))
      (node (ref "U26") (pin "10") (pinfunction "C_10") (pintype "unspecified"))
    )
    (net (code "94") (name "/SA11") (class "Default")
      (node (ref "D39") (pin "1") (pinfunction "1_1") (pintype "unspecified"))
      (node (ref "U26") (pin "9") (pinfunction "D_9") (pintype "unspecified"))
    )
    (net (code "95") (name "/SA12") (class "Default")
      (node (ref "D41") (pin "1") (pinfunction "1_1") (pintype "unspecified"))
      (node (ref "U29") (pin "15") (pinfunction "A_15") (pintype "unspecified"))
    )
    (net (code "96") (name "/SA13") (class "Default")
      (node (ref "D43") (pin "1") (pinfunction "1_1") (pintype "unspecified"))
      (node (ref "U29") (pin "1") (pinfunction "B_1") (pintype "unspecified"))
    )
    (net (code "97") (name "/SA14") (class "Default")
      (node (ref "D45") (pin "1") (pinfunction "1_1") (pintype "unspecified"))
      (node (ref "U29") (pin "10") (pinfunction "C_10") (pintype "unspecified"))
    )
    (net (code "98") (name "/SA15") (class "Default")
      (node (ref "D47") (pin "1") (pinfunction "1_1") (pintype "unspecified"))
      (node (ref "U29") (pin "9") (pinfunction "D_9") (pintype "unspecified"))
    )
    (net (code "99") (name "/SA16") (class "Default")
      (node (ref "D49") (pin "1") (pinfunction "1_1") (pintype "unspecified"))
      (node (ref "U33") (pin "15") (pinfunction "A_15") (pintype "unspecified"))
    )
    (net (code "100") (name "/SA17") (class "Default")
      (node (ref "D51") (pin "1") (pinfunction "1_1") (pintype "unspecified"))
      (node (ref "U33") (pin "1") (pinfunction "B_1") (pintype "unspecified"))
    )
    (net (code "101") (name "/SA18") (class "Default")
      (node (ref "D53") (pin "1") (pinfunction "1_1") (pintype "unspecified"))
      (node (ref "U33") (pin "10") (pinfunction "C_10") (pintype "unspecified"))
    )
    (net (code "102") (name "/SA19") (class "Default")
      (node (ref "D55") (pin "1") (pinfunction "1_1") (pintype "unspecified"))
      (node (ref "U33") (pin "9") (pinfunction "D_9") (pintype "unspecified"))
    )
    (net (code "103") (name "/SD") (class "Default")
      (node (ref "D62") (pin "1") (pinfunction "1_1") (pintype "unspecified"))
      (node (ref "D67") (pin "2") (pinfunction "2_2") (pintype "unspecified"))
      (node (ref "U17") (pin "11") (pinfunction "LOAD#_11") (pintype "unspecified"))
      (node (ref "U22") (pin "11") (pinfunction "LOAD#_11") (pintype "unspecified"))
    )
    (net (code "104") (name "/SD0") (class "Default")
      (node (ref "D32") (pin "1") (pinfunction "1_1") (pintype "unspecified"))
      (node (ref "P1") (pin "2") (pinfunction "2_2") (pintype "unspecified"))
      (node (ref "U17") (pin "15") (pinfunction "A_15") (pintype "unspecified"))
    )
    (net (code "105") (name "/SD1") (class "Default")
      (node (ref "D29") (pin "1") (pinfunction "1_1") (pintype "unspecified"))
      (node (ref "P1") (pin "3") (pinfunction "3_3") (pintype "unspecified"))
      (node (ref "U17") (pin "1") (pinfunction "B_1") (pintype "unspecified"))
    )
    (net (code "106") (name "/SD2") (class "Default")
      (node (ref "D26") (pin "1") (pinfunction "1_1") (pintype "unspecified"))
      (node (ref "P1") (pin "4") (pinfunction "4_4") (pintype "unspecified"))
      (node (ref "U17") (pin "10") (pinfunction "C_10") (pintype "unspecified"))
    )
    (net (code "107") (name "/SD3") (class "Default")
      (node (ref "D22") (pin "1") (pinfunction "1_1") (pintype "unspecified"))
      (node (ref "P1") (pin "5") (pinfunction "5_5") (pintype "unspecified"))
      (node (ref "U17") (pin "9") (pinfunction "D_9") (pintype "unspecified"))
    )
    (net (code "108") (name "/SD4") (class "Default")
      (node (ref "D18") (pin "1") (pinfunction "1_1") (pintype "unspecified"))
      (node (ref "P1") (pin "6") (pinfunction "6_6") (pintype "unspecified"))
      (node (ref "U22") (pin "15") (pinfunction "A_15") (pintype "unspecified"))
    )
    (net (code "109") (name "/SD5") (class "Default")
      (node (ref "D14") (pin "1") (pinfunction "1_1") (pintype "unspecified"))
      (node (ref "P1") (pin "7") (pinfunction "7_7") (pintype "unspecified"))
      (node (ref "U22") (pin "1") (pinfunction "B_1") (pintype "unspecified"))
    )
    (net (code "110") (name "/SD6") (class "Default")
      (node (ref "D10") (pin "1") (pinfunction "1_1") (pintype "unspecified"))
      (node (ref "P1") (pin "8") (pinfunction "8_8") (pintype "unspecified"))
      (node (ref "U22") (pin "10") (pinfunction "C_10") (pintype "unspecified"))
    )
    (net (code "111") (name "/SD7") (class "Default")
      (node (ref "D6") (pin "1") (pinfunction "1_1") (pintype "unspecified"))
      (node (ref "P1") (pin "9") (pinfunction "9_9") (pintype "unspecified"))
      (node (ref "U22") (pin "9") (pinfunction "D_9") (pintype "unspecified"))
    )
    (net (code "112") (name "/ST+-") (class "Default")
      (node (ref "U20") (pin "10") (pinfunction "Y5_10") (pintype "unspecified"))
      (node (ref "U27") (pin "14") (pinfunction "CLK_14") (pintype "unspecified"))
      (node (ref "U6") (pin "6") (pinfunction "2Y_6") (pintype "unspecified"))
    )
    (net (code "113") (name "/ST-{slash}+") (class "Default")
      (node (ref "U15") (pin "6") (pinfunction "2Y_6") (pintype "unspecified"))
      (node (ref "U15") (pin "9") (pinfunction "3B_9") (pintype "unspecified"))
      (node (ref "U27") (pin "5") (pinfunction "D/U#_5") (pintype "unspecified"))
      (node (ref "U30") (pin "5") (pinfunction "D/U#_5") (pintype "unspecified"))
      (node (ref "U34") (pin "5") (pinfunction "D/U#_5") (pintype "unspecified"))
    )
    (net (code "114") (name "/ST0WE") (class "Default")
      (node (ref "U25") (pin "9") (pinfunction "Y6_9") (pintype "unspecified"))
      (node (ref "U5") (pin "4") (pinfunction "2A_4") (pintype "unspecified"))
    )
    (net (code "115") (name "/ST0WE#") (class "Default")
      (node (ref "U3") (pin "27") (pinfunction "WE#_27") (pintype "unspecified"))
      (node (ref "U5") (pin "6") (pinfunction "2Y_6") (pintype "unspecified"))
    )
    (net (code "116") (name "/ST1WE") (class "Default")
      (node (ref "U19") (pin "6") (pinfunction "2Y_6") (pintype "unspecified"))
      (node (ref "U25") (pin "7") (pinfunction "Y7_7") (pintype "unspecified"))
    )
    (net (code "117") (name "/ST1WE#") (class "Default")
      (node (ref "U19") (pin "4") (pinfunction "2A_4") (pintype "unspecified"))
      (node (ref "U7") (pin "27") (pinfunction "WE#_27") (pintype "unspecified"))
    )
    (net (code "118") (name "/ST2WE") (class "Default")
      (node (ref "U19") (pin "3") (pinfunction "1Y_3") (pintype "unspecified"))
      (node (ref "U20") (pin "14") (pinfunction "Y1_14") (pintype "unspecified"))
      (node (ref "U36") (pin "1") (pinfunction "1A_1") (pintype "unspecified"))
      (node (ref "U36") (pin "10") (pinfunction "3B_10") (pintype "unspecified"))
      (node (ref "U36") (pin "13") (pinfunction "4B_13") (pintype "unspecified"))
      (node (ref "U36") (pin "4") (pinfunction "2A_4") (pintype "unspecified"))
    )
    (net (code "119") (name "/ST2WE#") (class "Default")
      (node (ref "U13") (pin "27") (pinfunction "WE#_27") (pintype "unspecified"))
      (node (ref "U19") (pin "1") (pinfunction "1A_1") (pintype "unspecified"))
    )
    (net (code "120") (name "/STA0") (class "Default")
      (node (ref "U13") (pin "10") (pinfunction "A0_10") (pintype "unspecified"))
      (node (ref "U27") (pin "3") (pinfunction "QA_3") (pintype "unspecified"))
      (node (ref "U3") (pin "10") (pinfunction "A0_10") (pintype "unspecified"))
      (node (ref "U7") (pin "10") (pinfunction "A0_10") (pintype "unspecified"))
    )
    (net (code "121") (name "/STA1") (class "Default")
      (node (ref "U13") (pin "9") (pinfunction "A1_9") (pintype "unspecified"))
      (node (ref "U27") (pin "2") (pinfunction "QB_2") (pintype "unspecified"))
      (node (ref "U3") (pin "9") (pinfunction "A1_9") (pintype "unspecified"))
      (node (ref "U7") (pin "9") (pinfunction "A1_9") (pintype "unspecified"))
    )
    (net (code "122") (name "/STA2") (class "Default")
      (node (ref "U13") (pin "8") (pinfunction "A2_8") (pintype "unspecified"))
      (node (ref "U27") (pin "6") (pinfunction "QC_6") (pintype "unspecified"))
      (node (ref "U3") (pin "8") (pinfunction "A2_8") (pintype "unspecified"))
      (node (ref "U7") (pin "8") (pinfunction "A2_8") (pintype "unspecified"))
    )
    (net (code "123") (name "/STA3") (class "Default")
      (node (ref "U13") (pin "7") (pinfunction "A3_7") (pintype "unspecified"))
      (node (ref "U27") (pin "7") (pinfunction "QD_7") (pintype "unspecified"))
      (node (ref "U3") (pin "7") (pinfunction "A3_7") (pintype "unspecified"))
      (node (ref "U7") (pin "7") (pinfunction "A3_7") (pintype "unspecified"))
    )
    (net (code "124") (name "/STA4") (class "Default")
      (node (ref "U13") (pin "6") (pinfunction "A4_6") (pintype "unspecified"))
      (node (ref "U3") (pin "6") (pinfunction "A4_6") (pintype "unspecified"))
      (node (ref "U30") (pin "3") (pinfunction "QA_3") (pintype "unspecified"))
      (node (ref "U7") (pin "6") (pinfunction "A4_6") (pintype "unspecified"))
    )
    (net (code "125") (name "/STA5") (class "Default")
      (node (ref "U13") (pin "5") (pinfunction "A5_5") (pintype "unspecified"))
      (node (ref "U3") (pin "5") (pinfunction "A5_5") (pintype "unspecified"))
      (node (ref "U30") (pin "2") (pinfunction "QB_2") (pintype "unspecified"))
      (node (ref "U7") (pin "5") (pinfunction "A5_5") (pintype "unspecified"))
    )
    (net (code "126") (name "/STA6") (class "Default")
      (node (ref "U13") (pin "4") (pinfunction "A6_4") (pintype "unspecified"))
      (node (ref "U3") (pin "4") (pinfunction "A6_4") (pintype "unspecified"))
      (node (ref "U30") (pin "6") (pinfunction "QC_6") (pintype "unspecified"))
      (node (ref "U7") (pin "4") (pinfunction "A6_4") (pintype "unspecified"))
    )
    (net (code "127") (name "/STA7") (class "Default")
      (node (ref "U13") (pin "3") (pinfunction "A7_3") (pintype "unspecified"))
      (node (ref "U3") (pin "3") (pinfunction "A7_3") (pintype "unspecified"))
      (node (ref "U30") (pin "7") (pinfunction "QD_7") (pintype "unspecified"))
      (node (ref "U7") (pin "3") (pinfunction "A7_3") (pintype "unspecified"))
    )
    (net (code "128") (name "/STA8") (class "Default")
      (node (ref "U13") (pin "25") (pinfunction "A8_25") (pintype "unspecified"))
      (node (ref "U3") (pin "25") (pinfunction "A8_25") (pintype "unspecified"))
      (node (ref "U34") (pin "3") (pinfunction "QA_3") (pintype "unspecified"))
      (node (ref "U7") (pin "25") (pinfunction "A8_25") (pintype "unspecified"))
    )
    (net (code "129") (name "/STA9") (class "Default")
      (node (ref "U13") (pin "24") (pinfunction "A9_24") (pintype "unspecified"))
      (node (ref "U3") (pin "24") (pinfunction "A9_24") (pintype "unspecified"))
      (node (ref "U34") (pin "2") (pinfunction "QB_2") (pintype "unspecified"))
      (node (ref "U7") (pin "24") (pinfunction "A9_24") (pintype "unspecified"))
    )
    (net (code "130") (name "/STA10") (class "Default")
      (node (ref "U13") (pin "21") (pinfunction "A10_21") (pintype "unspecified"))
      (node (ref "U3") (pin "21") (pinfunction "A10_21") (pintype "unspecified"))
      (node (ref "U34") (pin "6") (pinfunction "QC_6") (pintype "unspecified"))
      (node (ref "U7") (pin "21") (pinfunction "A10_21") (pintype "unspecified"))
    )
    (net (code "131") (name "/STA11") (class "Default")
      (node (ref "U13") (pin "23") (pinfunction "A11_23") (pintype "unspecified"))
      (node (ref "U3") (pin "23") (pinfunction "A11_23") (pintype "unspecified"))
      (node (ref "U34") (pin "7") (pinfunction "QD_7") (pintype "unspecified"))
      (node (ref "U7") (pin "23") (pinfunction "A11_23") (pintype "unspecified"))
    )
    (net (code "132") (name "/STOE") (class "Default")
      (node (ref "D66") (pin "2") (pinfunction "2_2") (pintype "unspecified"))
      (node (ref "D68") (pin "2") (pinfunction "2_2") (pintype "unspecified"))
      (node (ref "U20") (pin "13") (pinfunction "Y2_13") (pintype "unspecified"))
      (node (ref "U5") (pin "12") (pinfunction "4B_12") (pintype "unspecified"))
      (node (ref "U6") (pin "11") (pinfunction "4Y_11") (pintype "unspecified"))
    )
    (net (code "133") (name "/STOE#") (class "Default")
      (node (ref "U13") (pin "22") (pinfunction "OE#_22") (pintype "unspecified"))
      (node (ref "U3") (pin "22") (pinfunction "OE#_22") (pintype "unspecified"))
      (node (ref "U5") (pin "11") (pinfunction "4Y_11") (pintype "unspecified"))
      (node (ref "U7") (pin "22") (pinfunction "OE#_22") (pintype "unspecified"))
    )
    (net (code "134") (name "/ZERO") (class "Default")
      (node (ref "U2") (pin "8") (pinfunction "3Y_8") (pintype "unspecified"))
      (node (ref "U6") (pin "13") (pinfunction "4B_13") (pintype "unspecified"))
    )
    (net (code "135") (name "GND") (class "Default")
      (node (ref "C2") (pin "1") (pinfunction "1_1") (pintype "unspecified"))
      (node (ref "C3") (pin "1") (pinfunction "1_1") (pintype "unspecified"))
      (node (ref "DC1") (pin "3") (pinfunction "3_3") (pintype "unspecified"))
      (node (ref "LED1") (pin "2") (pinfunction "2_2") (pintype "unspecified"))
      (node (ref "P1") (pin "20") (pinfunction "20_20") (pintype "unspecified"))
      (node (ref "R3") (pin "1") (pinfunction "1_1") (pintype "unspecified"))
      (node (ref "R4") (pin "1") (pinfunction "1_1") (pintype "unspecified"))
      (node (ref "U1") (pin "7") (pinfunction "GND_7") (pintype "unspecified"))
      (node (ref "U10") (pin "7") (pinfunction "GND_7") (pintype "unspecified"))
      (node (ref "U11") (pin "7") (pinfunction "GND_7") (pintype "unspecified"))
      (node (ref "U12") (pin "7") (pinfunction "GND_7") (pintype "unspecified"))
      (node (ref "U13") (pin "14") (pinfunction "GND_14") (pintype "unspecified"))
      (node (ref "U13") (pin "20") (pinfunction "CE#_20") (pintype "unspecified"))
      (node (ref "U14") (pin "7") (pinfunction "GND_7") (pintype "unspecified"))
      (node (ref "U15") (pin "7") (pinfunction "GND_7") (pintype "unspecified"))
      (node (ref "U16") (pin "4") (pinfunction "CTEN#_4") (pintype "unspecified"))
      (node (ref "U16") (pin "5") (pinfunction "D/U#_5") (pintype "unspecified"))
      (node (ref "U16") (pin "8") (pinfunction "GND_8") (pintype "unspecified"))
      (node (ref "U17") (pin "4") (pinfunction "CTEN#_4") (pintype "unspecified"))
      (node (ref "U17") (pin "8") (pinfunction "GND_8") (pintype "unspecified"))
      (node (ref "U18") (pin "4") (pinfunction "CTEN#_4") (pintype "unspecified"))
      (node (ref "U18") (pin "8") (pinfunction "GND_8") (pintype "unspecified"))
      (node (ref "U19") (pin "7") (pinfunction "GND_7") (pintype "unspecified"))
      (node (ref "U2") (pin "7") (pinfunction "GND_7") (pintype "unspecified"))
      (node (ref "U20") (pin "5") (pinfunction "G#2B_5") (pintype "unspecified"))
      (node (ref "U20") (pin "8") (pinfunction "GND_8") (pintype "unspecified"))
      (node (ref "U21") (pin "4") (pinfunction "CTEN#_4") (pintype "unspecified"))
      (node (ref "U21") (pin "5") (pinfunction "D/U#_5") (pintype "unspecified"))
      (node (ref "U21") (pin "8") (pinfunction "GND_8") (pintype "unspecified"))
      (node (ref "U22") (pin "4") (pinfunction "CTEN#_4") (pintype "unspecified"))
      (node (ref "U22") (pin "8") (pinfunction "GND_8") (pintype "unspecified"))
      (node (ref "U23") (pin "4") (pinfunction "CTEN#_4") (pintype "unspecified"))
      (node (ref "U23") (pin "8") (pinfunction "GND_8") (pintype "unspecified"))
      (node (ref "U24") (pin "16") (pinfunction "GND_16") (pintype "unspecified"))
      (node (ref "U25") (pin "5") (pinfunction "G#2B_5") (pintype "unspecified"))
      (node (ref "U25") (pin "8") (pinfunction "GND_8") (pintype "unspecified"))
      (node (ref "U26") (pin "4") (pinfunction "CTEN#_4") (pintype "unspecified"))
      (node (ref "U26") (pin "5") (pinfunction "D/U#_5") (pintype "unspecified"))
      (node (ref "U26") (pin "8") (pinfunction "GND_8") (pintype "unspecified"))
      (node (ref "U27") (pin "4") (pinfunction "CTEN#_4") (pintype "unspecified"))
      (node (ref "U27") (pin "8") (pinfunction "GND_8") (pintype "unspecified"))
      (node (ref "U28") (pin "4") (pinfunction "CTEN#_4") (pintype "unspecified"))
      (node (ref "U28") (pin "8") (pinfunction "GND_8") (pintype "unspecified"))
      (node (ref "U29") (pin "4") (pinfunction "CTEN#_4") (pintype "unspecified"))
      (node (ref "U29") (pin "5") (pinfunction "D/U#_5") (pintype "unspecified"))
      (node (ref "U29") (pin "8") (pinfunction "GND_8") (pintype "unspecified"))
      (node (ref "U3") (pin "14") (pinfunction "GND_14") (pintype "unspecified"))
      (node (ref "U3") (pin "20") (pinfunction "CE#_20") (pintype "unspecified"))
      (node (ref "U30") (pin "4") (pinfunction "CTEN#_4") (pintype "unspecified"))
      (node (ref "U30") (pin "8") (pinfunction "GND_8") (pintype "unspecified"))
      (node (ref "U31") (pin "4") (pinfunction "CTEN#_4") (pintype "unspecified"))
      (node (ref "U31") (pin "8") (pinfunction "GND_8") (pintype "unspecified"))
      (node (ref "U32") (pin "16") (pinfunction "GND_16") (pintype "unspecified"))
      (node (ref "U33") (pin "4") (pinfunction "CTEN#_4") (pintype "unspecified"))
      (node (ref "U33") (pin "5") (pinfunction "D/U#_5") (pintype "unspecified"))
      (node (ref "U33") (pin "8") (pinfunction "GND_8") (pintype "unspecified"))
      (node (ref "U34") (pin "4") (pinfunction "CTEN#_4") (pintype "unspecified"))
      (node (ref "U34") (pin "8") (pinfunction "GND_8") (pintype "unspecified"))
      (node (ref "U35") (pin "4") (pinfunction "CTEN#_4") (pintype "unspecified"))
      (node (ref "U35") (pin "8") (pinfunction "GND_8") (pintype "unspecified"))
      (node (ref "U36") (pin "7") (pinfunction "GND_7") (pintype "unspecified"))
      (node (ref "U4") (pin "14") (pinfunction "GND_14") (pintype "unspecified"))
      (node (ref "U5") (pin "7") (pinfunction "GND_7") (pintype "unspecified"))
      (node (ref "U6") (pin "7") (pinfunction "GND_7") (pintype "unspecified"))
      (node (ref "U7") (pin "14") (pinfunction "GND_14") (pintype "unspecified"))
      (node (ref "U7") (pin "20") (pinfunction "CE#_20") (pintype "unspecified"))
      (node (ref "U8") (pin "14") (pinfunction "GND_14") (pintype "unspecified"))
      (node (ref "U9") (pin "7") (pinfunction "GND_7") (pintype "unspecified"))
      (node (ref "Y1") (pin "1") (pinfunction "P1_1") (pintype "unspecified"))
    )
    (net (code "136") (name "Net-(DC1-Pad1)") (class "Default")
      (node (ref "DC1") (pin "1") (pinfunction "1_1") (pintype "unspecified"))
      (node (ref "SW1") (pin "2") (pinfunction "2_2") (pintype "unspecified"))
    )
    (net (code "137") (name "Net-(F1-Pad2)") (class "Default")
      (node (ref "F1") (pin "2") (pinfunction "2_2") (pintype "unspecified"))
      (node (ref "LED1") (pin "1") (pinfunction "1_1") (pintype "unspecified"))
    )
    (net (code "138") (name "Net-(Q1-B)") (class "Default")
      (node (ref "C2") (pin "2") (pinfunction "2_2") (pintype "unspecified"))
      (node (ref "Q1") (pin "2") (pinfunction "B_2") (pintype "unspecified"))
      (node (ref "R2") (pin "1") (pinfunction "1_1") (pintype "unspecified"))
      (node (ref "R3") (pin "2") (pinfunction "2_2") (pintype "unspecified"))
    )
    (net (code "139") (name "Net-(Q1-E)") (class "Default")
      (node (ref "C1") (pin "1") (pinfunction "1_1") (pintype "unspecified"))
      (node (ref "C3") (pin "2") (pinfunction "2_2") (pintype "unspecified"))
      (node (ref "Q1") (pin "1") (pinfunction "E_1") (pintype "unspecified"))
      (node (ref "R4") (pin "2") (pinfunction "2_2") (pintype "unspecified"))
    )
    (net (code "140") (name "Net-(U3-I{slash}O0)") (class "Default")
      (node (ref "D25") (pin "2") (pinfunction "2_2") (pintype "unspecified"))
      (node (ref "D27") (pin "1") (pinfunction "1_1") (pintype "unspecified"))
      (node (ref "U3") (pin "11") (pinfunction "I/O0_11") (pintype "unspecified"))
    )
    (net (code "141") (name "Net-(U3-I{slash}O1)") (class "Default")
      (node (ref "D21") (pin "2") (pinfunction "2_2") (pintype "unspecified"))
      (node (ref "D23") (pin "1") (pinfunction "1_1") (pintype "unspecified"))
      (node (ref "U3") (pin "12") (pinfunction "I/O1_12") (pintype "unspecified"))
    )
    (net (code "142") (name "Net-(U3-I{slash}O2)") (class "Default")
      (node (ref "D17") (pin "2") (pinfunction "2_2") (pintype "unspecified"))
      (node (ref "D19") (pin "1") (pinfunction "1_1") (pintype "unspecified"))
      (node (ref "U3") (pin "13") (pinfunction "I/O2_13") (pintype "unspecified"))
    )
    (net (code "143") (name "Net-(U3-I{slash}O3)") (class "Default")
      (node (ref "D13") (pin "2") (pinfunction "2_2") (pintype "unspecified"))
      (node (ref "D15") (pin "1") (pinfunction "1_1") (pintype "unspecified"))
      (node (ref "U3") (pin "15") (pinfunction "I/O3_15") (pintype "unspecified"))
    )
    (net (code "144") (name "Net-(U3-I{slash}O4)") (class "Default")
      (node (ref "D11") (pin "1") (pinfunction "1_1") (pintype "unspecified"))
      (node (ref "D9") (pin "2") (pinfunction "2_2") (pintype "unspecified"))
      (node (ref "U3") (pin "16") (pinfunction "I/O4_16") (pintype "unspecified"))
    )
    (net (code "145") (name "Net-(U3-I{slash}O5)") (class "Default")
      (node (ref "D5") (pin "2") (pinfunction "2_2") (pintype "unspecified"))
      (node (ref "D7") (pin "1") (pinfunction "1_1") (pintype "unspecified"))
      (node (ref "U3") (pin "17") (pinfunction "I/O5_17") (pintype "unspecified"))
    )
    (net (code "146") (name "Net-(U3-I{slash}O6)") (class "Default")
      (node (ref "D3") (pin "2") (pinfunction "2_2") (pintype "unspecified"))
      (node (ref "D4") (pin "1") (pinfunction "1_1") (pintype "unspecified"))
      (node (ref "U3") (pin "18") (pinfunction "I/O6_18") (pintype "unspecified"))
    )
    (net (code "147") (name "Net-(U3-I{slash}O7)") (class "Default")
      (node (ref "D1") (pin "2") (pinfunction "2_2") (pintype "unspecified"))
      (node (ref "D2") (pin "1") (pinfunction "1_1") (pintype "unspecified"))
      (node (ref "U3") (pin "19") (pinfunction "I/O7_19") (pintype "unspecified"))
    )
    (net (code "148") (name "Net-(U4-I{slash}O0)") (class "Default")
      (node (ref "D32") (pin "2") (pinfunction "2_2") (pintype "unspecified"))
      (node (ref "D34") (pin "1") (pinfunction "1_1") (pintype "unspecified"))
      (node (ref "U4") (pin "11") (pinfunction "I/O0_11") (pintype "unspecified"))
      (node (ref "U8") (pin "11") (pinfunction "I/O0_11") (pintype "unspecified"))
    )
    (net (code "149") (name "Net-(U4-I{slash}O1)") (class "Default")
      (node (ref "D29") (pin "2") (pinfunction "2_2") (pintype "unspecified"))
      (node (ref "D30") (pin "1") (pinfunction "1_1") (pintype "unspecified"))
      (node (ref "U4") (pin "12") (pinfunction "I/O1_12") (pintype "unspecified"))
      (node (ref "U8") (pin "12") (pinfunction "I/O1_12") (pintype "unspecified"))
    )
    (net (code "150") (name "Net-(U4-I{slash}O2)") (class "Default")
      (node (ref "D26") (pin "2") (pinfunction "2_2") (pintype "unspecified"))
      (node (ref "D28") (pin "1") (pinfunction "1_1") (pintype "unspecified"))
      (node (ref "U4") (pin "13") (pinfunction "I/O2_13") (pintype "unspecified"))
      (node (ref "U8") (pin "13") (pinfunction "I/O2_13") (pintype "unspecified"))
    )
    (net (code "151") (name "Net-(U4-I{slash}O3)") (class "Default")
      (node (ref "D22") (pin "2") (pinfunction "2_2") (pintype "unspecified"))
      (node (ref "D24") (pin "1") (pinfunction "1_1") (pintype "unspecified"))
      (node (ref "U4") (pin "15") (pinfunction "I/O3_15") (pintype "unspecified"))
      (node (ref "U8") (pin "15") (pinfunction "I/O3_15") (pintype "unspecified"))
    )
    (net (code "152") (name "Net-(U4-I{slash}O4)") (class "Default")
      (node (ref "D18") (pin "2") (pinfunction "2_2") (pintype "unspecified"))
      (node (ref "D20") (pin "1") (pinfunction "1_1") (pintype "unspecified"))
      (node (ref "U4") (pin "16") (pinfunction "I/O4_16") (pintype "unspecified"))
      (node (ref "U8") (pin "16") (pinfunction "I/O4_16") (pintype "unspecified"))
    )
    (net (code "153") (name "Net-(U4-I{slash}O5)") (class "Default")
      (node (ref "D14") (pin "2") (pinfunction "2_2") (pintype "unspecified"))
      (node (ref "D16") (pin "1") (pinfunction "1_1") (pintype "unspecified"))
      (node (ref "U4") (pin "17") (pinfunction "I/O5_17") (pintype "unspecified"))
      (node (ref "U8") (pin "17") (pinfunction "I/O5_17") (pintype "unspecified"))
    )
    (net (code "154") (name "Net-(U4-I{slash}O6)") (class "Default")
      (node (ref "D10") (pin "2") (pinfunction "2_2") (pintype "unspecified"))
      (node (ref "D12") (pin "1") (pinfunction "1_1") (pintype "unspecified"))
      (node (ref "U4") (pin "18") (pinfunction "I/O6_18") (pintype "unspecified"))
      (node (ref "U8") (pin "18") (pinfunction "I/O6_18") (pintype "unspecified"))
    )
    (net (code "155") (name "Net-(U4-I{slash}O7)") (class "Default")
      (node (ref "D6") (pin "2") (pinfunction "2_2") (pintype "unspecified"))
      (node (ref "D8") (pin "1") (pinfunction "1_1") (pintype "unspecified"))
      (node (ref "U4") (pin "19") (pinfunction "I/O7_19") (pintype "unspecified"))
      (node (ref "U8") (pin "19") (pinfunction "I/O7_19") (pintype "unspecified"))
    )
    (net (code "156") (name "Net-(U7-I{slash}O0)") (class "Default")
      (node (ref "D47") (pin "2") (pinfunction "2_2") (pintype "unspecified"))
      (node (ref "D48") (pin "1") (pinfunction "1_1") (pintype "unspecified"))
      (node (ref "U7") (pin "11") (pinfunction "I/O0_11") (pintype "unspecified"))
    )
    (net (code "157") (name "Net-(U7-I{slash}O1)") (class "Default")
      (node (ref "D45") (pin "2") (pinfunction "2_2") (pintype "unspecified"))
      (node (ref "D46") (pin "1") (pinfunction "1_1") (pintype "unspecified"))
      (node (ref "U7") (pin "12") (pinfunction "I/O1_12") (pintype "unspecified"))
    )
    (net (code "158") (name "Net-(U7-I{slash}O2)") (class "Default")
      (node (ref "D43") (pin "2") (pinfunction "2_2") (pintype "unspecified"))
      (node (ref "D44") (pin "1") (pinfunction "1_1") (pintype "unspecified"))
      (node (ref "U7") (pin "13") (pinfunction "I/O2_13") (pintype "unspecified"))
    )
    (net (code "159") (name "Net-(U7-I{slash}O3)") (class "Default")
      (node (ref "D41") (pin "2") (pinfunction "2_2") (pintype "unspecified"))
      (node (ref "D42") (pin "1") (pinfunction "1_1") (pintype "unspecified"))
      (node (ref "U7") (pin "15") (pinfunction "I/O3_15") (pintype "unspecified"))
    )
    (net (code "160") (name "Net-(U7-I{slash}O4)") (class "Default")
      (node (ref "D39") (pin "2") (pinfunction "2_2") (pintype "unspecified"))
      (node (ref "D40") (pin "1") (pinfunction "1_1") (pintype "unspecified"))
      (node (ref "U7") (pin "16") (pinfunction "I/O4_16") (pintype "unspecified"))
    )
    (net (code "161") (name "Net-(U7-I{slash}O5)") (class "Default")
      (node (ref "D37") (pin "2") (pinfunction "2_2") (pintype "unspecified"))
      (node (ref "D38") (pin "1") (pinfunction "1_1") (pintype "unspecified"))
      (node (ref "U7") (pin "17") (pinfunction "I/O5_17") (pintype "unspecified"))
    )
    (net (code "162") (name "Net-(U7-I{slash}O6)") (class "Default")
      (node (ref "D35") (pin "2") (pinfunction "2_2") (pintype "unspecified"))
      (node (ref "D36") (pin "1") (pinfunction "1_1") (pintype "unspecified"))
      (node (ref "U7") (pin "18") (pinfunction "I/O6_18") (pintype "unspecified"))
    )
    (net (code "163") (name "Net-(U7-I{slash}O7)") (class "Default")
      (node (ref "D31") (pin "2") (pinfunction "2_2") (pintype "unspecified"))
      (node (ref "D33") (pin "1") (pinfunction "1_1") (pintype "unspecified"))
      (node (ref "U7") (pin "19") (pinfunction "I/O7_19") (pintype "unspecified"))
    )
    (net (code "164") (name "Net-(U10-1Y)") (class "Default")
      (node (ref "U10") (pin "3") (pinfunction "1Y_3") (pintype "unspecified"))
      (node (ref "U11") (pin "4") (pinfunction "2A_4") (pintype "unspecified"))
    )
    (net (code "165") (name "Net-(U10-2Y)") (class "Default")
      (node (ref "U10") (pin "6") (pinfunction "2Y_6") (pintype "unspecified"))
      (node (ref "U12") (pin "1") (pinfunction "1A_1") (pintype "unspecified"))
    )
    (net (code "166") (name "Net-(U10-3Y)") (class "Default")
      (node (ref "U10") (pin "8") (pinfunction "3Y_8") (pintype "unspecified"))
      (node (ref "U12") (pin "10") (pinfunction "3B_10") (pintype "unspecified"))
    )
    (net (code "167") (name "Net-(U10-4Y)") (class "Default")
      (node (ref "U10") (pin "11") (pinfunction "4Y_11") (pintype "unspecified"))
      (node (ref "U12") (pin "13") (pinfunction "4B_13") (pintype "unspecified"))
    )
    (net (code "168") (name "Net-(U11-1A)") (class "Default")
      (node (ref "U11") (pin "1") (pinfunction "1A_1") (pintype "unspecified"))
      (node (ref "U9") (pin "3") (pinfunction "1Y_3") (pintype "unspecified"))
    )
    (net (code "169") (name "Net-(U11-1B)") (class "Default")
      (node (ref "U11") (pin "2") (pinfunction "1B_2") (pintype "unspecified"))
      (node (ref "U9") (pin "6") (pinfunction "2Y_6") (pintype "unspecified"))
    )
    (net (code "170") (name "Net-(U11-1Y)") (class "Default")
      (node (ref "U11") (pin "3") (pinfunction "1Y_3") (pintype "unspecified"))
      (node (ref "U11") (pin "5") (pinfunction "2B_5") (pintype "unspecified"))
    )
    (net (code "171") (name "Net-(U11-2Y)") (class "Default")
      (node (ref "U11") (pin "6") (pinfunction "2Y_6") (pintype "unspecified"))
      (node (ref "U11") (pin "9") (pinfunction "3A_9") (pintype "unspecified"))
    )
    (net (code "172") (name "Net-(U11-3B)") (class "Default")
      (node (ref "U11") (pin "10") (pinfunction "3B_10") (pintype "unspecified"))
      (node (ref "U9") (pin "8") (pinfunction "3Y_8") (pintype "unspecified"))
    )
    (net (code "173") (name "Net-(U11-3Y)") (class "Default")
      (node (ref "U11") (pin "12") (pinfunction "4A_12") (pintype "unspecified"))
      (node (ref "U11") (pin "8") (pinfunction "3Y_8") (pintype "unspecified"))
    )
    (net (code "174") (name "Net-(U11-4B)") (class "Default")
      (node (ref "U11") (pin "13") (pinfunction "4B_13") (pintype "unspecified"))
      (node (ref "U9") (pin "11") (pinfunction "4Y_11") (pintype "unspecified"))
    )
    (net (code "175") (name "Net-(U11-4Y)") (class "Default")
      (node (ref "U11") (pin "11") (pinfunction "4Y_11") (pintype "unspecified"))
      (node (ref "U12") (pin "2") (pinfunction "1B_2") (pintype "unspecified"))
    )
    (net (code "176") (name "Net-(U12-1Y)") (class "Default")
      (node (ref "U12") (pin "12") (pinfunction "4A_12") (pintype "unspecified"))
      (node (ref "U12") (pin "3") (pinfunction "1Y_3") (pintype "unspecified"))
    )
    (net (code "177") (name "Net-(U12-3A)") (class "Default")
      (node (ref "U12") (pin "11") (pinfunction "4Y_11") (pintype "unspecified"))
      (node (ref "U12") (pin "9") (pinfunction "3A_9") (pintype "unspecified"))
    )
    (net (code "178") (name "Net-(U12-3Y)") (class "Default")
      (node (ref "U12") (pin "8") (pinfunction "3Y_8") (pintype "unspecified"))
      (node (ref "U2") (pin "10") (pinfunction "3A_10") (pintype "unspecified"))
    )
    (net (code "179") (name "Net-(U13-I{slash}O4)") (class "Default")
      (node (ref "D55") (pin "2") (pinfunction "2_2") (pintype "unspecified"))
      (node (ref "D56") (pin "1") (pinfunction "1_1") (pintype "unspecified"))
      (node (ref "U13") (pin "16") (pinfunction "I/O4_16") (pintype "unspecified"))
    )
    (net (code "180") (name "Net-(U13-I{slash}O5)") (class "Default")
      (node (ref "D53") (pin "2") (pinfunction "2_2") (pintype "unspecified"))
      (node (ref "D54") (pin "1") (pinfunction "1_1") (pintype "unspecified"))
      (node (ref "U13") (pin "17") (pinfunction "I/O5_17") (pintype "unspecified"))
    )
    (net (code "181") (name "Net-(U13-I{slash}O6)") (class "Default")
      (node (ref "D51") (pin "2") (pinfunction "2_2") (pintype "unspecified"))
      (node (ref "D52") (pin "1") (pinfunction "1_1") (pintype "unspecified"))
      (node (ref "U13") (pin "18") (pinfunction "I/O6_18") (pintype "unspecified"))
    )
    (net (code "182") (name "Net-(U13-I{slash}O7)") (class "Default")
      (node (ref "D49") (pin "2") (pinfunction "2_2") (pintype "unspecified"))
      (node (ref "D50") (pin "1") (pinfunction "1_1") (pintype "unspecified"))
      (node (ref "U13") (pin "19") (pinfunction "I/O7_19") (pintype "unspecified"))
    )
    (net (code "183") (name "Net-(U16-MAX{slash}MIN)") (class "Default")
      (node (ref "U16") (pin "12") (pinfunction "MAX/MIN_12") (pintype "unspecified"))
      (node (ref "U21") (pin "14") (pinfunction "CLK_14") (pintype "unspecified"))
    )
    (net (code "184") (name "Net-(U17-MAX{slash}MIN)") (class "Default")
      (node (ref "U17") (pin "12") (pinfunction "MAX/MIN_12") (pintype "unspecified"))
      (node (ref "U22") (pin "14") (pinfunction "CLK_14") (pintype "unspecified"))
    )
    (net (code "185") (name "Net-(U18-MAX{slash}MIN)") (class "Default")
      (node (ref "U18") (pin "12") (pinfunction "MAX/MIN_12") (pintype "unspecified"))
      (node (ref "U23") (pin "14") (pinfunction "CLK_14") (pintype "unspecified"))
    )
    (net (code "186") (name "Net-(U21-MAX{slash}MIN)") (class "Default")
      (node (ref "U21") (pin "12") (pinfunction "MAX/MIN_12") (pintype "unspecified"))
      (node (ref "U26") (pin "14") (pinfunction "CLK_14") (pintype "unspecified"))
    )
    (net (code "187") (name "Net-(U23-MAX{slash}MIN)") (class "Default")
      (node (ref "U23") (pin "12") (pinfunction "MAX/MIN_12") (pintype "unspecified"))
      (node (ref "U28") (pin "14") (pinfunction "CLK_14") (pintype "unspecified"))
    )
    (net (code "188") (name "Net-(U26-MAX{slash}MIN)") (class "Default")
      (node (ref "U26") (pin "12") (pinfunction "MAX/MIN_12") (pintype "unspecified"))
      (node (ref "U29") (pin "14") (pinfunction "CLK_14") (pintype "unspecified"))
    )
    (net (code "189") (name "Net-(U27-MAX{slash}MIN)") (class "Default")
      (node (ref "U27") (pin "12") (pinfunction "MAX/MIN_12") (pintype "unspecified"))
      (node (ref "U30") (pin "14") (pinfunction "CLK_14") (pintype "unspecified"))
    )
    (net (code "190") (name "Net-(U28-MAX{slash}MIN)") (class "Default")
      (node (ref "U28") (pin "12") (pinfunction "MAX/MIN_12") (pintype "unspecified"))
      (node (ref "U31") (pin "14") (pinfunction "CLK_14") (pintype "unspecified"))
    )
    (net (code "191") (name "Net-(U29-MAX{slash}MIN)") (class "Default")
      (node (ref "U29") (pin "12") (pinfunction "MAX/MIN_12") (pintype "unspecified"))
      (node (ref "U33") (pin "14") (pinfunction "CLK_14") (pintype "unspecified"))
    )
    (net (code "192") (name "Net-(U30-MAX{slash}MIN)") (class "Default")
      (node (ref "U30") (pin "12") (pinfunction "MAX/MIN_12") (pintype "unspecified"))
      (node (ref "U34") (pin "14") (pinfunction "CLK_14") (pintype "unspecified"))
    )
    (net (code "193") (name "Net-(U35-LOAD#)") (class "Default")
      (node (ref "D65") (pin "1") (pinfunction "1_1") (pintype "unspecified"))
      (node (ref "U35") (pin "11") (pinfunction "LOAD#_11") (pintype "unspecified"))
    )
    (net (code "194") (name "VCC") (class "Default")
      (node (ref "F1") (pin "1") (pinfunction "1_1") (pintype "unspecified"))
      (node (ref "P1") (pin "1") (pinfunction "1_1") (pintype "unspecified"))
      (node (ref "R1") (pin "2") (pinfunction "2_2") (pintype "unspecified"))
      (node (ref "R2") (pin "2") (pinfunction "2_2") (pintype "unspecified"))
      (node (ref "SW1") (pin "3") (pinfunction "3_3") (pintype "unspecified"))
      (node (ref "U1") (pin "1") (pinfunction "1A_1") (pintype "unspecified"))
      (node (ref "U1") (pin "10") (pinfunction "3A_10") (pintype "unspecified"))
      (node (ref "U1") (pin "13") (pinfunction "4A_13") (pintype "unspecified"))
      (node (ref "U1") (pin "14") (pinfunction "VCC_14") (pintype "unspecified"))
      (node (ref "U1") (pin "5") (pinfunction "2B_5") (pintype "unspecified"))
      (node (ref "U10") (pin "12") (pinfunction "4A_12") (pintype "unspecified"))
      (node (ref "U10") (pin "14") (pinfunction "VCC_14") (pintype "unspecified"))
      (node (ref "U10") (pin "2") (pinfunction "1B_2") (pintype "unspecified"))
      (node (ref "U10") (pin "5") (pinfunction "2B_5") (pintype "unspecified"))
      (node (ref "U10") (pin "9") (pinfunction "3A_9") (pintype "unspecified"))
      (node (ref "U11") (pin "14") (pinfunction "VCC_14") (pintype "unspecified"))
      (node (ref "U12") (pin "14") (pinfunction "VCC_14") (pintype "unspecified"))
      (node (ref "U13") (pin "28") (pinfunction "VDD_28") (pintype "unspecified"))
      (node (ref "U14") (pin "14") (pinfunction "VCC_14") (pintype "unspecified"))
      (node (ref "U15") (pin "10") (pinfunction "3A_10") (pintype "unspecified"))
      (node (ref "U15") (pin "12") (pinfunction "4B_12") (pintype "unspecified"))
      (node (ref "U15") (pin "14") (pinfunction "VCC_14") (pintype "unspecified"))
      (node (ref "U15") (pin "2") (pinfunction "1B_2") (pintype "unspecified"))
      (node (ref "U15") (pin "4") (pinfunction "2A_4") (pintype "unspecified"))
      (node (ref "U16") (pin "16") (pinfunction "VCC_16") (pintype "unspecified"))
      (node (ref "U17") (pin "16") (pinfunction "VCC_16") (pintype "unspecified"))
      (node (ref "U18") (pin "16") (pinfunction "VCC_16") (pintype "unspecified"))
      (node (ref "U19") (pin "14") (pinfunction "VCC_14") (pintype "unspecified"))
      (node (ref "U19") (pin "2") (pinfunction "1B_2") (pintype "unspecified"))
      (node (ref "U19") (pin "5") (pinfunction "2B_5") (pintype "unspecified"))
      (node (ref "U2") (pin "1") (pinfunction "1A_1") (pintype "unspecified"))
      (node (ref "U2") (pin "12") (pinfunction "4B_12") (pintype "unspecified"))
      (node (ref "U2") (pin "14") (pinfunction "VCC_14") (pintype "unspecified"))
      (node (ref "U2") (pin "9") (pinfunction "3B_9") (pintype "unspecified"))
      (node (ref "U20") (pin "16") (pinfunction "VCC_16") (pintype "unspecified"))
      (node (ref "U20") (pin "6") (pinfunction "G1_6") (pintype "unspecified"))
      (node (ref "U21") (pin "16") (pinfunction "VCC_16") (pintype "unspecified"))
      (node (ref "U22") (pin "16") (pinfunction "VCC_16") (pintype "unspecified"))
      (node (ref "U23") (pin "16") (pinfunction "VCC_16") (pintype "unspecified"))
      (node (ref "U24") (pin "1") (pinfunction "Vpp_1") (pintype "unspecified"))
      (node (ref "U24") (pin "32") (pinfunction "VCC_32") (pintype "unspecified"))
      (node (ref "U25") (pin "16") (pinfunction "VCC_16") (pintype "unspecified"))
      (node (ref "U25") (pin "6") (pinfunction "G1_6") (pintype "unspecified"))
      (node (ref "U26") (pin "16") (pinfunction "VCC_16") (pintype "unspecified"))
      (node (ref "U27") (pin "16") (pinfunction "VCC_16") (pintype "unspecified"))
      (node (ref "U28") (pin "16") (pinfunction "VCC_16") (pintype "unspecified"))
      (node (ref "U29") (pin "16") (pinfunction "VCC_16") (pintype "unspecified"))
      (node (ref "U3") (pin "28") (pinfunction "VDD_28") (pintype "unspecified"))
      (node (ref "U30") (pin "16") (pinfunction "VCC_16") (pintype "unspecified"))
      (node (ref "U31") (pin "16") (pinfunction "VCC_16") (pintype "unspecified"))
      (node (ref "U32") (pin "1") (pinfunction "Vpp_1") (pintype "unspecified"))
      (node (ref "U32") (pin "32") (pinfunction "VCC_32") (pintype "unspecified"))
      (node (ref "U33") (pin "16") (pinfunction "VCC_16") (pintype "unspecified"))
      (node (ref "U34") (pin "16") (pinfunction "VCC_16") (pintype "unspecified"))
      (node (ref "U35") (pin "16") (pinfunction "VCC_16") (pintype "unspecified"))
      (node (ref "U35") (pin "5") (pinfunction "D/U#_5") (pintype "unspecified"))
      (node (ref "U36") (pin "14") (pinfunction "VCC_14") (pintype "unspecified"))
      (node (ref "U4") (pin "28") (pinfunction "VDD_28") (pintype "unspecified"))
      (node (ref "U5") (pin "10") (pinfunction "3A_10") (pintype "unspecified"))
      (node (ref "U5") (pin "13") (pinfunction "4A_13") (pintype "unspecified"))
      (node (ref "U5") (pin "14") (pinfunction "VCC_14") (pintype "unspecified"))
      (node (ref "U5") (pin "2") (pinfunction "1B_2") (pintype "unspecified"))
      (node (ref "U5") (pin "5") (pinfunction "2B_5") (pintype "unspecified"))
      (node (ref "U6") (pin "1") (pinfunction "1A_1") (pintype "unspecified"))
      (node (ref "U6") (pin "14") (pinfunction "VCC_14") (pintype "unspecified"))
      (node (ref "U6") (pin "9") (pinfunction "3A_9") (pintype "unspecified"))
      (node (ref "U7") (pin "28") (pinfunction "VDD_28") (pintype "unspecified"))
      (node (ref "U8") (pin "28") (pinfunction "VDD_28") (pintype "unspecified"))
      (node (ref "U9") (pin "12") (pinfunction "4A_12") (pintype "unspecified"))
      (node (ref "U9") (pin "14") (pinfunction "VCC_14") (pintype "unspecified"))
      (node (ref "U9") (pin "2") (pinfunction "1B_2") (pintype "unspecified"))
      (node (ref "U9") (pin "5") (pinfunction "2B_5") (pintype "unspecified"))
      (node (ref "U9") (pin "9") (pinfunction "3A_9") (pintype "unspecified"))
    )
    (net (code "195") (name "unconnected-(DC1-Pad2)") (class "Default")
      (node (ref "DC1") (pin "2") (pinfunction "2_2") (pintype "unspecified+no_connect"))
    )
    (net (code "196") (name "unconnected-(SW1-Pad1)") (class "Default")
      (node (ref "SW1") (pin "1") (pinfunction "1_1") (pintype "unspecified+no_connect"))
    )
    (net (code "197") (name "unconnected-(SW1-Pad4)") (class "Default")
      (node (ref "SW1") (pin "4") (pinfunction "4_4") (pintype "unspecified+no_connect"))
    )
    (net (code "198") (name "unconnected-(SW1-Pad5)") (class "Default")
      (node (ref "SW1") (pin "5") (pinfunction "5_5") (pintype "unspecified+no_connect"))
    )
    (net (code "199") (name "unconnected-(U2-2A-Pad4)") (class "Default")
      (node (ref "U2") (pin "4") (pinfunction "2A_4") (pintype "unspecified+no_connect"))
    )
    (net (code "200") (name "unconnected-(U2-2B-Pad5)") (class "Default")
      (node (ref "U2") (pin "5") (pinfunction "2B_5") (pintype "unspecified+no_connect"))
    )
    (net (code "201") (name "unconnected-(U2-2Y-Pad6)") (class "Default")
      (node (ref "U2") (pin "6") (pinfunction "2Y_6") (pintype "unspecified+no_connect"))
    )
    (net (code "202") (name "unconnected-(U3-A12-Pad2)") (class "Default")
      (node (ref "U3") (pin "2") (pinfunction "A12_2") (pintype "unspecified+no_connect"))
    )
    (net (code "203") (name "unconnected-(U3-A13-Pad26)") (class "Default")
      (node (ref "U3") (pin "26") (pinfunction "A13_26") (pintype "unspecified+no_connect"))
    )
    (net (code "204") (name "unconnected-(U3-A14-Pad1)") (class "Default")
      (node (ref "U3") (pin "1") (pinfunction "A14_1") (pintype "unspecified+no_connect"))
    )
    (net (code "205") (name "unconnected-(U7-A12-Pad2)") (class "Default")
      (node (ref "U7") (pin "2") (pinfunction "A12_2") (pintype "unspecified+no_connect"))
    )
    (net (code "206") (name "unconnected-(U7-A13-Pad26)") (class "Default")
      (node (ref "U7") (pin "26") (pinfunction "A13_26") (pintype "unspecified+no_connect"))
    )
    (net (code "207") (name "unconnected-(U7-A14-Pad1)") (class "Default")
      (node (ref "U7") (pin "1") (pinfunction "A14_1") (pintype "unspecified+no_connect"))
    )
    (net (code "208") (name "unconnected-(U12-2A-Pad4)") (class "Default")
      (node (ref "U12") (pin "4") (pinfunction "2A_4") (pintype "unspecified+no_connect"))
    )
    (net (code "209") (name "unconnected-(U12-2B-Pad5)") (class "Default")
      (node (ref "U12") (pin "5") (pinfunction "2B_5") (pintype "unspecified+no_connect"))
    )
    (net (code "210") (name "unconnected-(U12-2Y-Pad6)") (class "Default")
      (node (ref "U12") (pin "6") (pinfunction "2Y_6") (pintype "unspecified+no_connect"))
    )
    (net (code "211") (name "unconnected-(U13-A12-Pad2)") (class "Default")
      (node (ref "U13") (pin "2") (pinfunction "A12_2") (pintype "unspecified+no_connect"))
    )
    (net (code "212") (name "unconnected-(U13-A13-Pad26)") (class "Default")
      (node (ref "U13") (pin "26") (pinfunction "A13_26") (pintype "unspecified+no_connect"))
    )
    (net (code "213") (name "unconnected-(U13-A14-Pad1)") (class "Default")
      (node (ref "U13") (pin "1") (pinfunction "A14_1") (pintype "unspecified+no_connect"))
    )
    (net (code "214") (name "unconnected-(U13-I{slash}O0-Pad11)") (class "Default")
      (node (ref "U13") (pin "11") (pinfunction "I/O0_11") (pintype "unspecified+no_connect"))
    )
    (net (code "215") (name "unconnected-(U13-I{slash}O1-Pad12)") (class "Default")
      (node (ref "U13") (pin "12") (pinfunction "I/O1_12") (pintype "unspecified+no_connect"))
    )
    (net (code "216") (name "unconnected-(U13-I{slash}O2-Pad13)") (class "Default")
      (node (ref "U13") (pin "13") (pinfunction "I/O2_13") (pintype "unspecified+no_connect"))
    )
    (net (code "217") (name "unconnected-(U13-I{slash}O3-Pad15)") (class "Default")
      (node (ref "U13") (pin "15") (pinfunction "I/O3_15") (pintype "unspecified+no_connect"))
    )
    (net (code "218") (name "unconnected-(U16-RCO#-Pad13)") (class "Default")
      (node (ref "U16") (pin "13") (pinfunction "RCO#_13") (pintype "unspecified+no_connect"))
    )
    (net (code "219") (name "unconnected-(U17-RCO#-Pad13)") (class "Default")
      (node (ref "U17") (pin "13") (pinfunction "RCO#_13") (pintype "unspecified+no_connect"))
    )
    (net (code "220") (name "unconnected-(U18-A-Pad15)") (class "Default")
      (node (ref "U18") (pin "15") (pinfunction "A_15") (pintype "unspecified+no_connect"))
    )
    (net (code "221") (name "unconnected-(U18-B-Pad1)") (class "Default")
      (node (ref "U18") (pin "1") (pinfunction "B_1") (pintype "unspecified+no_connect"))
    )
    (net (code "222") (name "unconnected-(U18-C-Pad10)") (class "Default")
      (node (ref "U18") (pin "10") (pinfunction "C_10") (pintype "unspecified+no_connect"))
    )
    (net (code "223") (name "unconnected-(U18-D-Pad9)") (class "Default")
      (node (ref "U18") (pin "9") (pinfunction "D_9") (pintype "unspecified+no_connect"))
    )
    (net (code "224") (name "unconnected-(U18-LOAD#-Pad11)") (class "Default")
      (node (ref "U18") (pin "11") (pinfunction "LOAD#_11") (pintype "unspecified+no_connect"))
    )
    (net (code "225") (name "unconnected-(U18-RCO#-Pad13)") (class "Default")
      (node (ref "U18") (pin "13") (pinfunction "RCO#_13") (pintype "unspecified+no_connect"))
    )
    (net (code "226") (name "unconnected-(U19-3A-Pad10)") (class "Default")
      (node (ref "U19") (pin "10") (pinfunction "3A_10") (pintype "unspecified+no_connect"))
    )
    (net (code "227") (name "unconnected-(U19-3B-Pad9)") (class "Default")
      (node (ref "U19") (pin "9") (pinfunction "3B_9") (pintype "unspecified+no_connect"))
    )
    (net (code "228") (name "unconnected-(U19-3Y-Pad8)") (class "Default")
      (node (ref "U19") (pin "8") (pinfunction "3Y_8") (pintype "unspecified+no_connect"))
    )
    (net (code "229") (name "unconnected-(U19-4A-Pad13)") (class "Default")
      (node (ref "U19") (pin "13") (pinfunction "4A_13") (pintype "unspecified+no_connect"))
    )
    (net (code "230") (name "unconnected-(U19-4B-Pad12)") (class "Default")
      (node (ref "U19") (pin "12") (pinfunction "4B_12") (pintype "unspecified+no_connect"))
    )
    (net (code "231") (name "unconnected-(U19-4Y-Pad11)") (class "Default")
      (node (ref "U19") (pin "11") (pinfunction "4Y_11") (pintype "unspecified+no_connect"))
    )
    (net (code "232") (name "unconnected-(U20-Y0-Pad15)") (class "Default")
      (node (ref "U20") (pin "15") (pinfunction "Y0_15") (pintype "unspecified+no_connect"))
    )
    (net (code "233") (name "unconnected-(U20-Y6-Pad9)") (class "Default")
      (node (ref "U20") (pin "9") (pinfunction "Y6_9") (pintype "unspecified+no_connect"))
    )
    (net (code "234") (name "unconnected-(U20-Y7-Pad7)") (class "Default")
      (node (ref "U20") (pin "7") (pinfunction "Y7_7") (pintype "unspecified+no_connect"))
    )
    (net (code "235") (name "unconnected-(U21-RCO#-Pad13)") (class "Default")
      (node (ref "U21") (pin "13") (pinfunction "RCO#_13") (pintype "unspecified+no_connect"))
    )
    (net (code "236") (name "unconnected-(U22-MAX{slash}MIN-Pad12)") (class "Default")
      (node (ref "U22") (pin "12") (pinfunction "MAX/MIN_12") (pintype "unspecified+no_connect"))
    )
    (net (code "237") (name "unconnected-(U22-RCO#-Pad13)") (class "Default")
      (node (ref "U22") (pin "13") (pinfunction "RCO#_13") (pintype "unspecified+no_connect"))
    )
    (net (code "238") (name "unconnected-(U23-A-Pad15)") (class "Default")
      (node (ref "U23") (pin "15") (pinfunction "A_15") (pintype "unspecified+no_connect"))
    )
    (net (code "239") (name "unconnected-(U23-B-Pad1)") (class "Default")
      (node (ref "U23") (pin "1") (pinfunction "B_1") (pintype "unspecified+no_connect"))
    )
    (net (code "240") (name "unconnected-(U23-C-Pad10)") (class "Default")
      (node (ref "U23") (pin "10") (pinfunction "C_10") (pintype "unspecified+no_connect"))
    )
    (net (code "241") (name "unconnected-(U23-D-Pad9)") (class "Default")
      (node (ref "U23") (pin "9") (pinfunction "D_9") (pintype "unspecified+no_connect"))
    )
    (net (code "242") (name "unconnected-(U23-LOAD#-Pad11)") (class "Default")
      (node (ref "U23") (pin "11") (pinfunction "LOAD#_11") (pintype "unspecified+no_connect"))
    )
    (net (code "243") (name "unconnected-(U23-RCO#-Pad13)") (class "Default")
      (node (ref "U23") (pin "13") (pinfunction "RCO#_13") (pintype "unspecified+no_connect"))
    )
    (net (code "244") (name "unconnected-(U26-RCO#-Pad13)") (class "Default")
      (node (ref "U26") (pin "13") (pinfunction "RCO#_13") (pintype "unspecified+no_connect"))
    )
    (net (code "245") (name "unconnected-(U27-A-Pad15)") (class "Default")
      (node (ref "U27") (pin "15") (pinfunction "A_15") (pintype "unspecified+no_connect"))
    )
    (net (code "246") (name "unconnected-(U27-B-Pad1)") (class "Default")
      (node (ref "U27") (pin "1") (pinfunction "B_1") (pintype "unspecified+no_connect"))
    )
    (net (code "247") (name "unconnected-(U27-C-Pad10)") (class "Default")
      (node (ref "U27") (pin "10") (pinfunction "C_10") (pintype "unspecified+no_connect"))
    )
    (net (code "248") (name "unconnected-(U27-D-Pad9)") (class "Default")
      (node (ref "U27") (pin "9") (pinfunction "D_9") (pintype "unspecified+no_connect"))
    )
    (net (code "249") (name "unconnected-(U27-LOAD#-Pad11)") (class "Default")
      (node (ref "U27") (pin "11") (pinfunction "LOAD#_11") (pintype "unspecified+no_connect"))
    )
    (net (code "250") (name "unconnected-(U27-RCO#-Pad13)") (class "Default")
      (node (ref "U27") (pin "13") (pinfunction "RCO#_13") (pintype "unspecified+no_connect"))
    )
    (net (code "251") (name "unconnected-(U28-A-Pad15)") (class "Default")
      (node (ref "U28") (pin "15") (pinfunction "A_15") (pintype "unspecified+no_connect"))
    )
    (net (code "252") (name "unconnected-(U28-B-Pad1)") (class "Default")
      (node (ref "U28") (pin "1") (pinfunction "B_1") (pintype "unspecified+no_connect"))
    )
    (net (code "253") (name "unconnected-(U28-C-Pad10)") (class "Default")
      (node (ref "U28") (pin "10") (pinfunction "C_10") (pintype "unspecified+no_connect"))
    )
    (net (code "254") (name "unconnected-(U28-D-Pad9)") (class "Default")
      (node (ref "U28") (pin "9") (pinfunction "D_9") (pintype "unspecified+no_connect"))
    )
    (net (code "255") (name "unconnected-(U28-LOAD#-Pad11)") (class "Default")
      (node (ref "U28") (pin "11") (pinfunction "LOAD#_11") (pintype "unspecified+no_connect"))
    )
    (net (code "256") (name "unconnected-(U28-RCO#-Pad13)") (class "Default")
      (node (ref "U28") (pin "13") (pinfunction "RCO#_13") (pintype "unspecified+no_connect"))
    )
    (net (code "257") (name "unconnected-(U29-RCO#-Pad13)") (class "Default")
      (node (ref "U29") (pin "13") (pinfunction "RCO#_13") (pintype "unspecified+no_connect"))
    )
    (net (code "258") (name "unconnected-(U30-A-Pad15)") (class "Default")
      (node (ref "U30") (pin "15") (pinfunction "A_15") (pintype "unspecified+no_connect"))
    )
    (net (code "259") (name "unconnected-(U30-B-Pad1)") (class "Default")
      (node (ref "U30") (pin "1") (pinfunction "B_1") (pintype "unspecified+no_connect"))
    )
    (net (code "260") (name "unconnected-(U30-C-Pad10)") (class "Default")
      (node (ref "U30") (pin "10") (pinfunction "C_10") (pintype "unspecified+no_connect"))
    )
    (net (code "261") (name "unconnected-(U30-D-Pad9)") (class "Default")
      (node (ref "U30") (pin "9") (pinfunction "D_9") (pintype "unspecified+no_connect"))
    )
    (net (code "262") (name "unconnected-(U30-LOAD#-Pad11)") (class "Default")
      (node (ref "U30") (pin "11") (pinfunction "LOAD#_11") (pintype "unspecified+no_connect"))
    )
    (net (code "263") (name "unconnected-(U30-RCO#-Pad13)") (class "Default")
      (node (ref "U30") (pin "13") (pinfunction "RCO#_13") (pintype "unspecified+no_connect"))
    )
    (net (code "264") (name "unconnected-(U31-A-Pad15)") (class "Default")
      (node (ref "U31") (pin "15") (pinfunction "A_15") (pintype "unspecified+no_connect"))
    )
    (net (code "265") (name "unconnected-(U31-B-Pad1)") (class "Default")
      (node (ref "U31") (pin "1") (pinfunction "B_1") (pintype "unspecified+no_connect"))
    )
    (net (code "266") (name "unconnected-(U31-C-Pad10)") (class "Default")
      (node (ref "U31") (pin "10") (pinfunction "C_10") (pintype "unspecified+no_connect"))
    )
    (net (code "267") (name "unconnected-(U31-D-Pad9)") (class "Default")
      (node (ref "U31") (pin "9") (pinfunction "D_9") (pintype "unspecified+no_connect"))
    )
    (net (code "268") (name "unconnected-(U31-LOAD#-Pad11)") (class "Default")
      (node (ref "U31") (pin "11") (pinfunction "LOAD#_11") (pintype "unspecified+no_connect"))
    )
    (net (code "269") (name "unconnected-(U31-MAX{slash}MIN-Pad12)") (class "Default")
      (node (ref "U31") (pin "12") (pinfunction "MAX/MIN_12") (pintype "unspecified+no_connect"))
    )
    (net (code "270") (name "unconnected-(U31-RCO#-Pad13)") (class "Default")
      (node (ref "U31") (pin "13") (pinfunction "RCO#_13") (pintype "unspecified+no_connect"))
    )
    (net (code "271") (name "unconnected-(U33-MAX{slash}MIN-Pad12)") (class "Default")
      (node (ref "U33") (pin "12") (pinfunction "MAX/MIN_12") (pintype "unspecified+no_connect"))
    )
    (net (code "272") (name "unconnected-(U33-RCO#-Pad13)") (class "Default")
      (node (ref "U33") (pin "13") (pinfunction "RCO#_13") (pintype "unspecified+no_connect"))
    )
    (net (code "273") (name "unconnected-(U34-A-Pad15)") (class "Default")
      (node (ref "U34") (pin "15") (pinfunction "A_15") (pintype "unspecified+no_connect"))
    )
    (net (code "274") (name "unconnected-(U34-B-Pad1)") (class "Default")
      (node (ref "U34") (pin "1") (pinfunction "B_1") (pintype "unspecified+no_connect"))
    )
    (net (code "275") (name "unconnected-(U34-C-Pad10)") (class "Default")
      (node (ref "U34") (pin "10") (pinfunction "C_10") (pintype "unspecified+no_connect"))
    )
    (net (code "276") (name "unconnected-(U34-D-Pad9)") (class "Default")
      (node (ref "U34") (pin "9") (pinfunction "D_9") (pintype "unspecified+no_connect"))
    )
    (net (code "277") (name "unconnected-(U34-LOAD#-Pad11)") (class "Default")
      (node (ref "U34") (pin "11") (pinfunction "LOAD#_11") (pintype "unspecified+no_connect"))
    )
    (net (code "278") (name "unconnected-(U34-MAX{slash}MIN-Pad12)") (class "Default")
      (node (ref "U34") (pin "12") (pinfunction "MAX/MIN_12") (pintype "unspecified+no_connect"))
    )
    (net (code "279") (name "unconnected-(U34-RCO#-Pad13)") (class "Default")
      (node (ref "U34") (pin "13") (pinfunction "RCO#_13") (pintype "unspecified+no_connect"))
    )
    (net (code "280") (name "unconnected-(U35-QA-Pad3)") (class "Default")
      (node (ref "U35") (pin "3") (pinfunction "QA_3") (pintype "unspecified+no_connect"))
    )
    (net (code "281") (name "unconnected-(U35-QB-Pad2)") (class "Default")
      (node (ref "U35") (pin "2") (pinfunction "QB_2") (pintype "unspecified+no_connect"))
    )
    (net (code "282") (name "unconnected-(U35-QC-Pad6)") (class "Default")
      (node (ref "U35") (pin "6") (pinfunction "QC_6") (pintype "unspecified+no_connect"))
    )
    (net (code "283") (name "unconnected-(U35-QD-Pad7)") (class "Default")
      (node (ref "U35") (pin "7") (pinfunction "QD_7") (pintype "unspecified+no_connect"))
    )
    (net (code "284") (name "unconnected-(U35-RCO#-Pad13)") (class "Default")
      (node (ref "U35") (pin "13") (pinfunction "RCO#_13") (pintype "unspecified+no_connect"))
    )
  )
)
